# 2.net
KiCad netlist of a schematic drawn in EasyEDA Pro
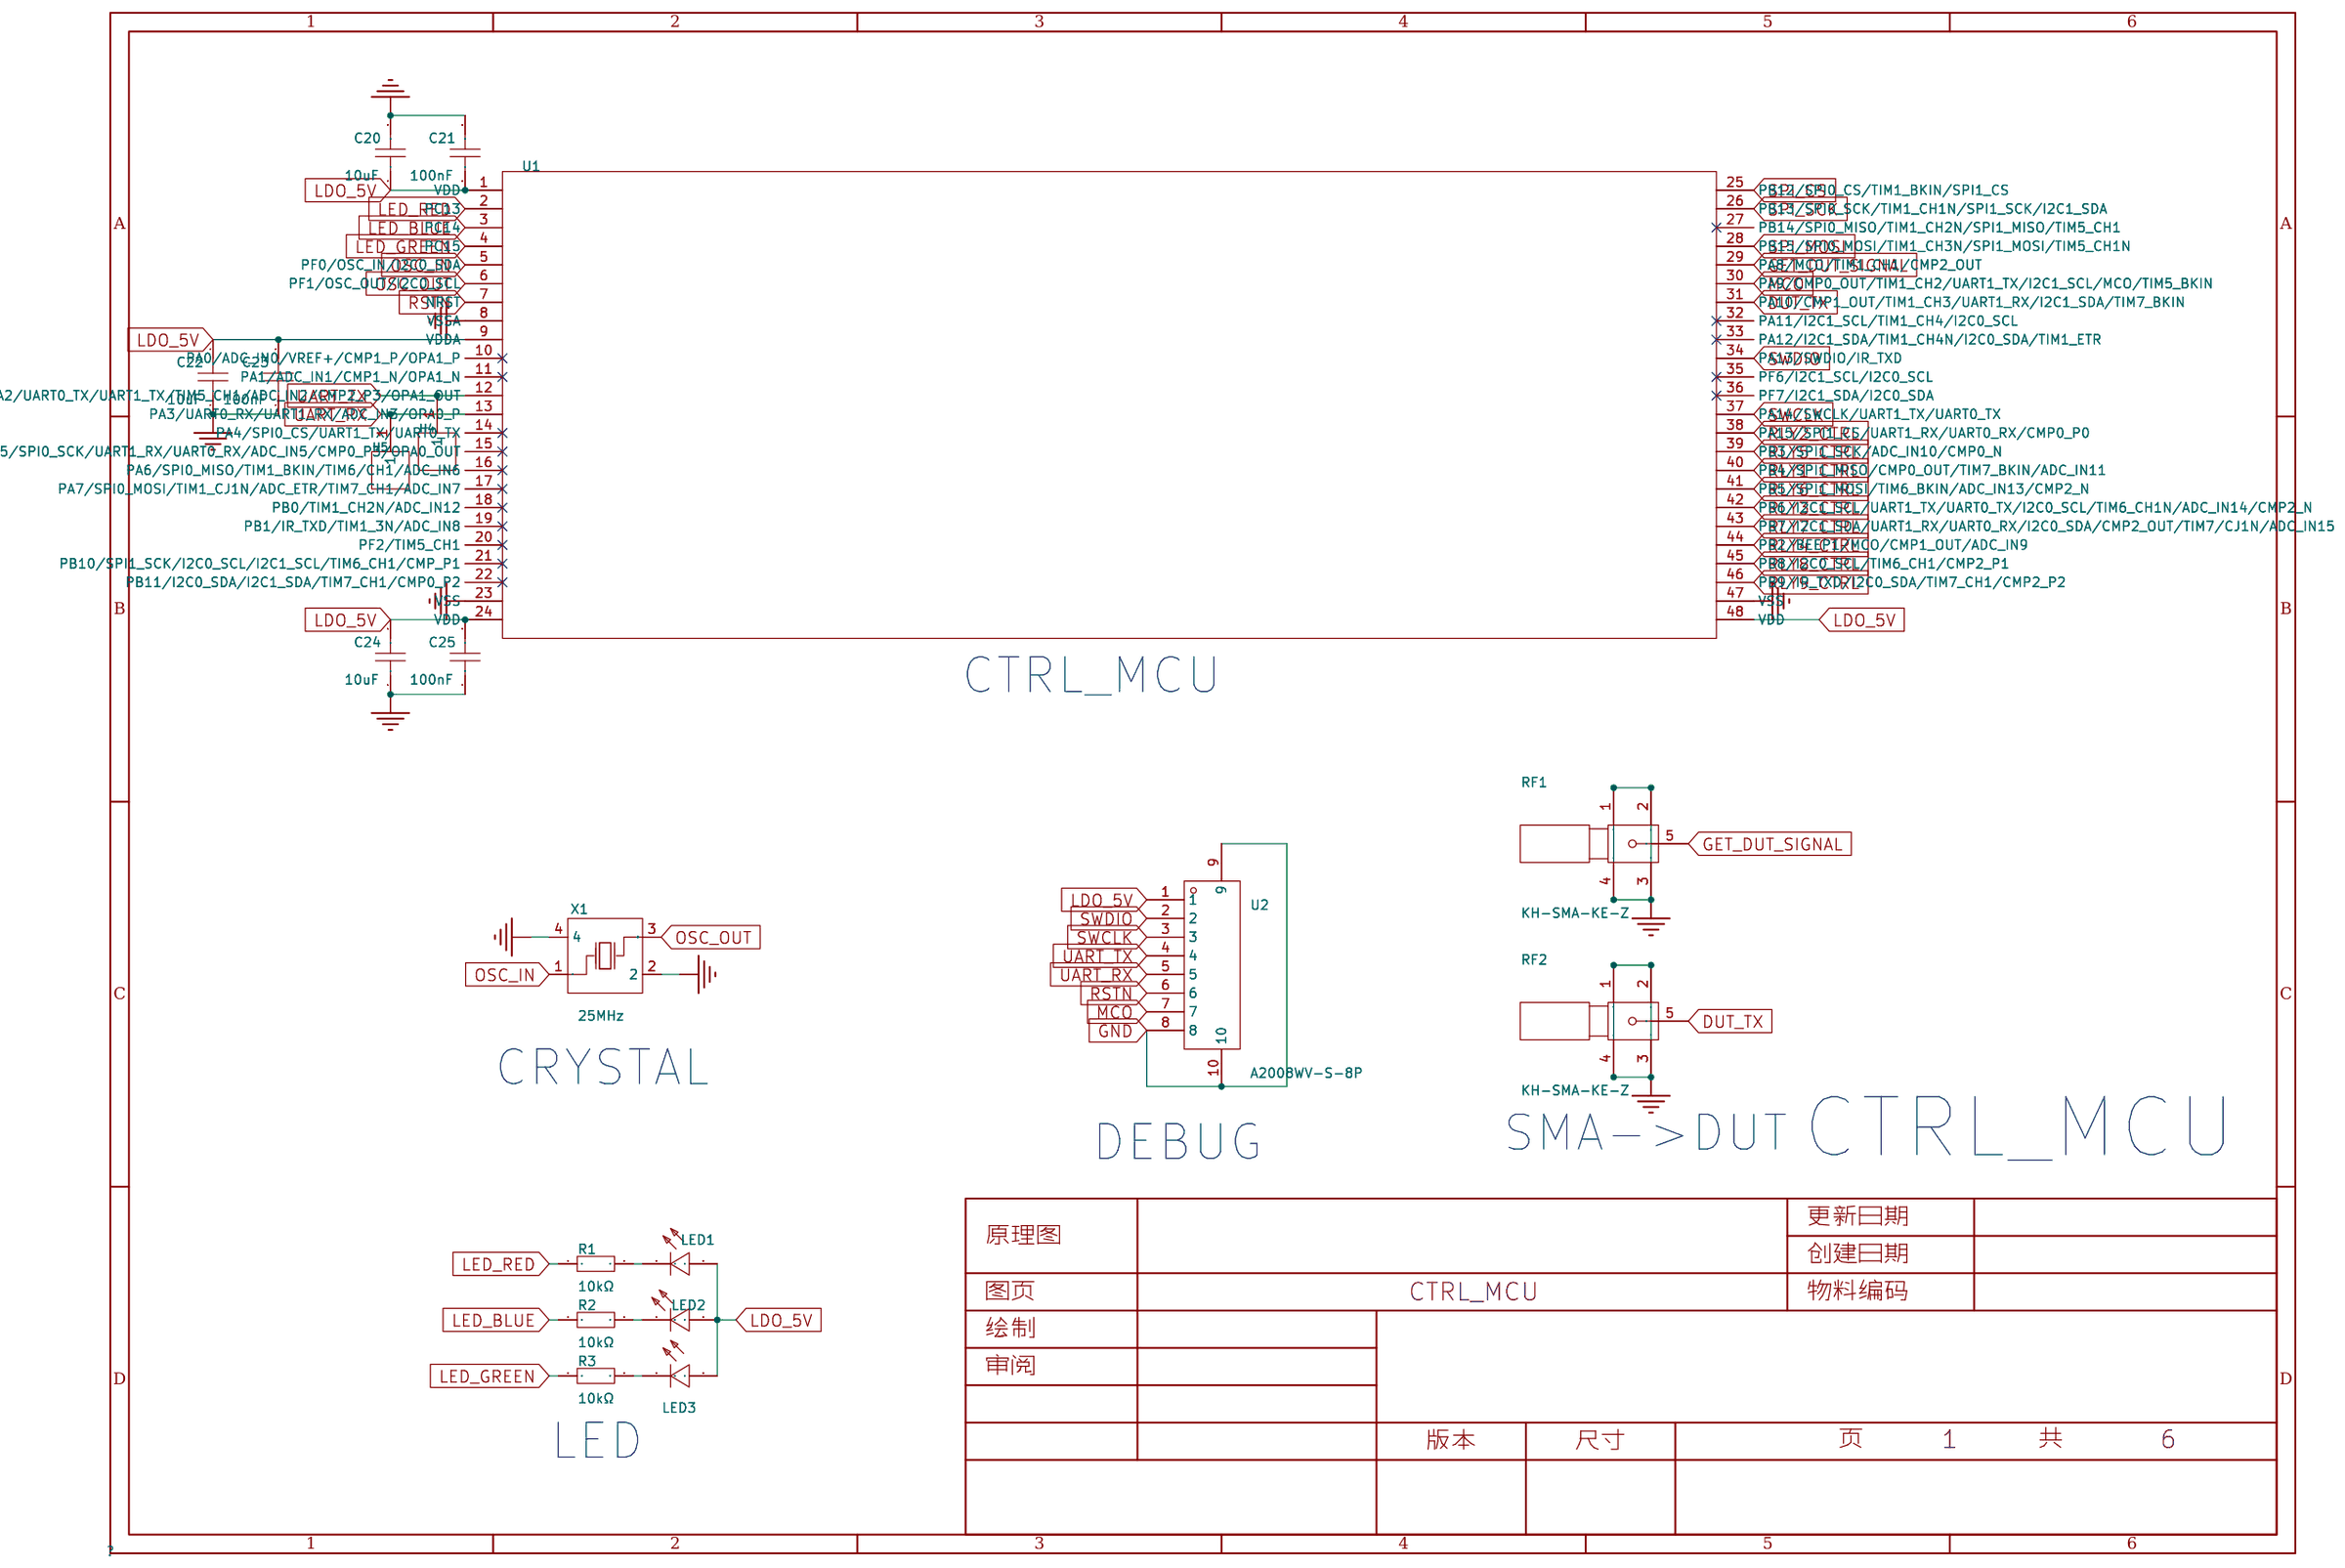
[diagram p0: CTRL_MCU]
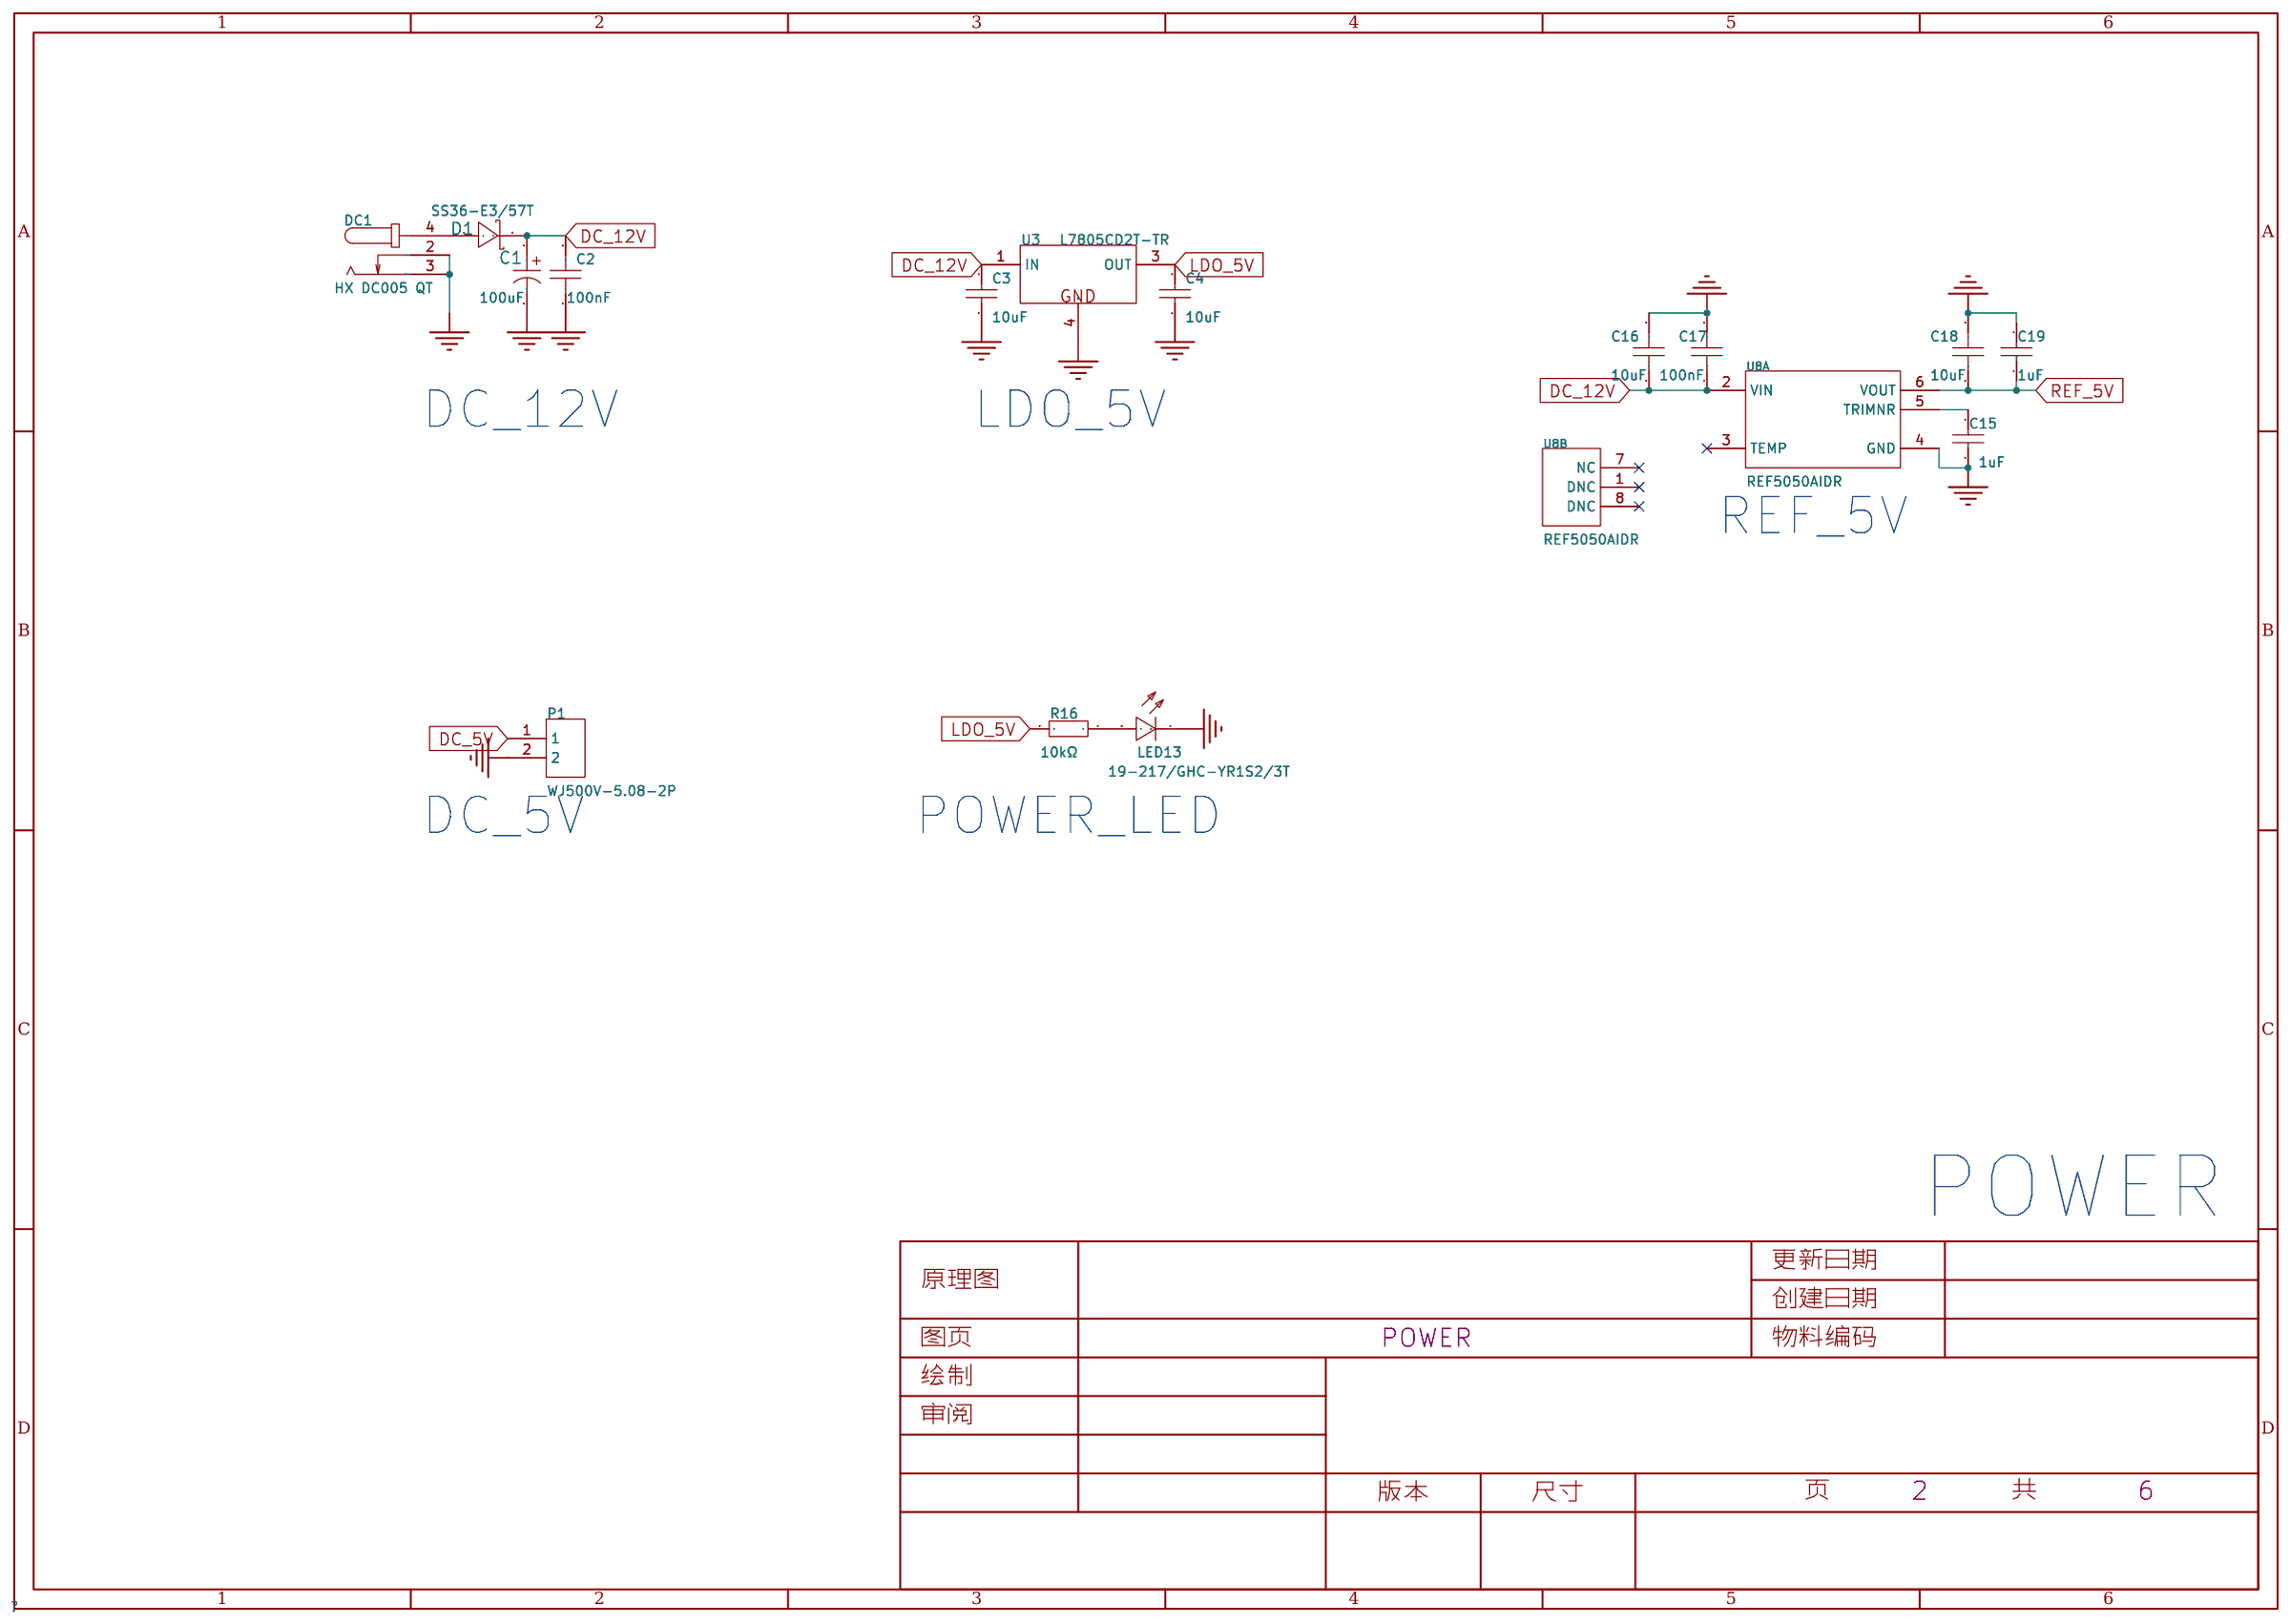
[diagram p1: POWER]
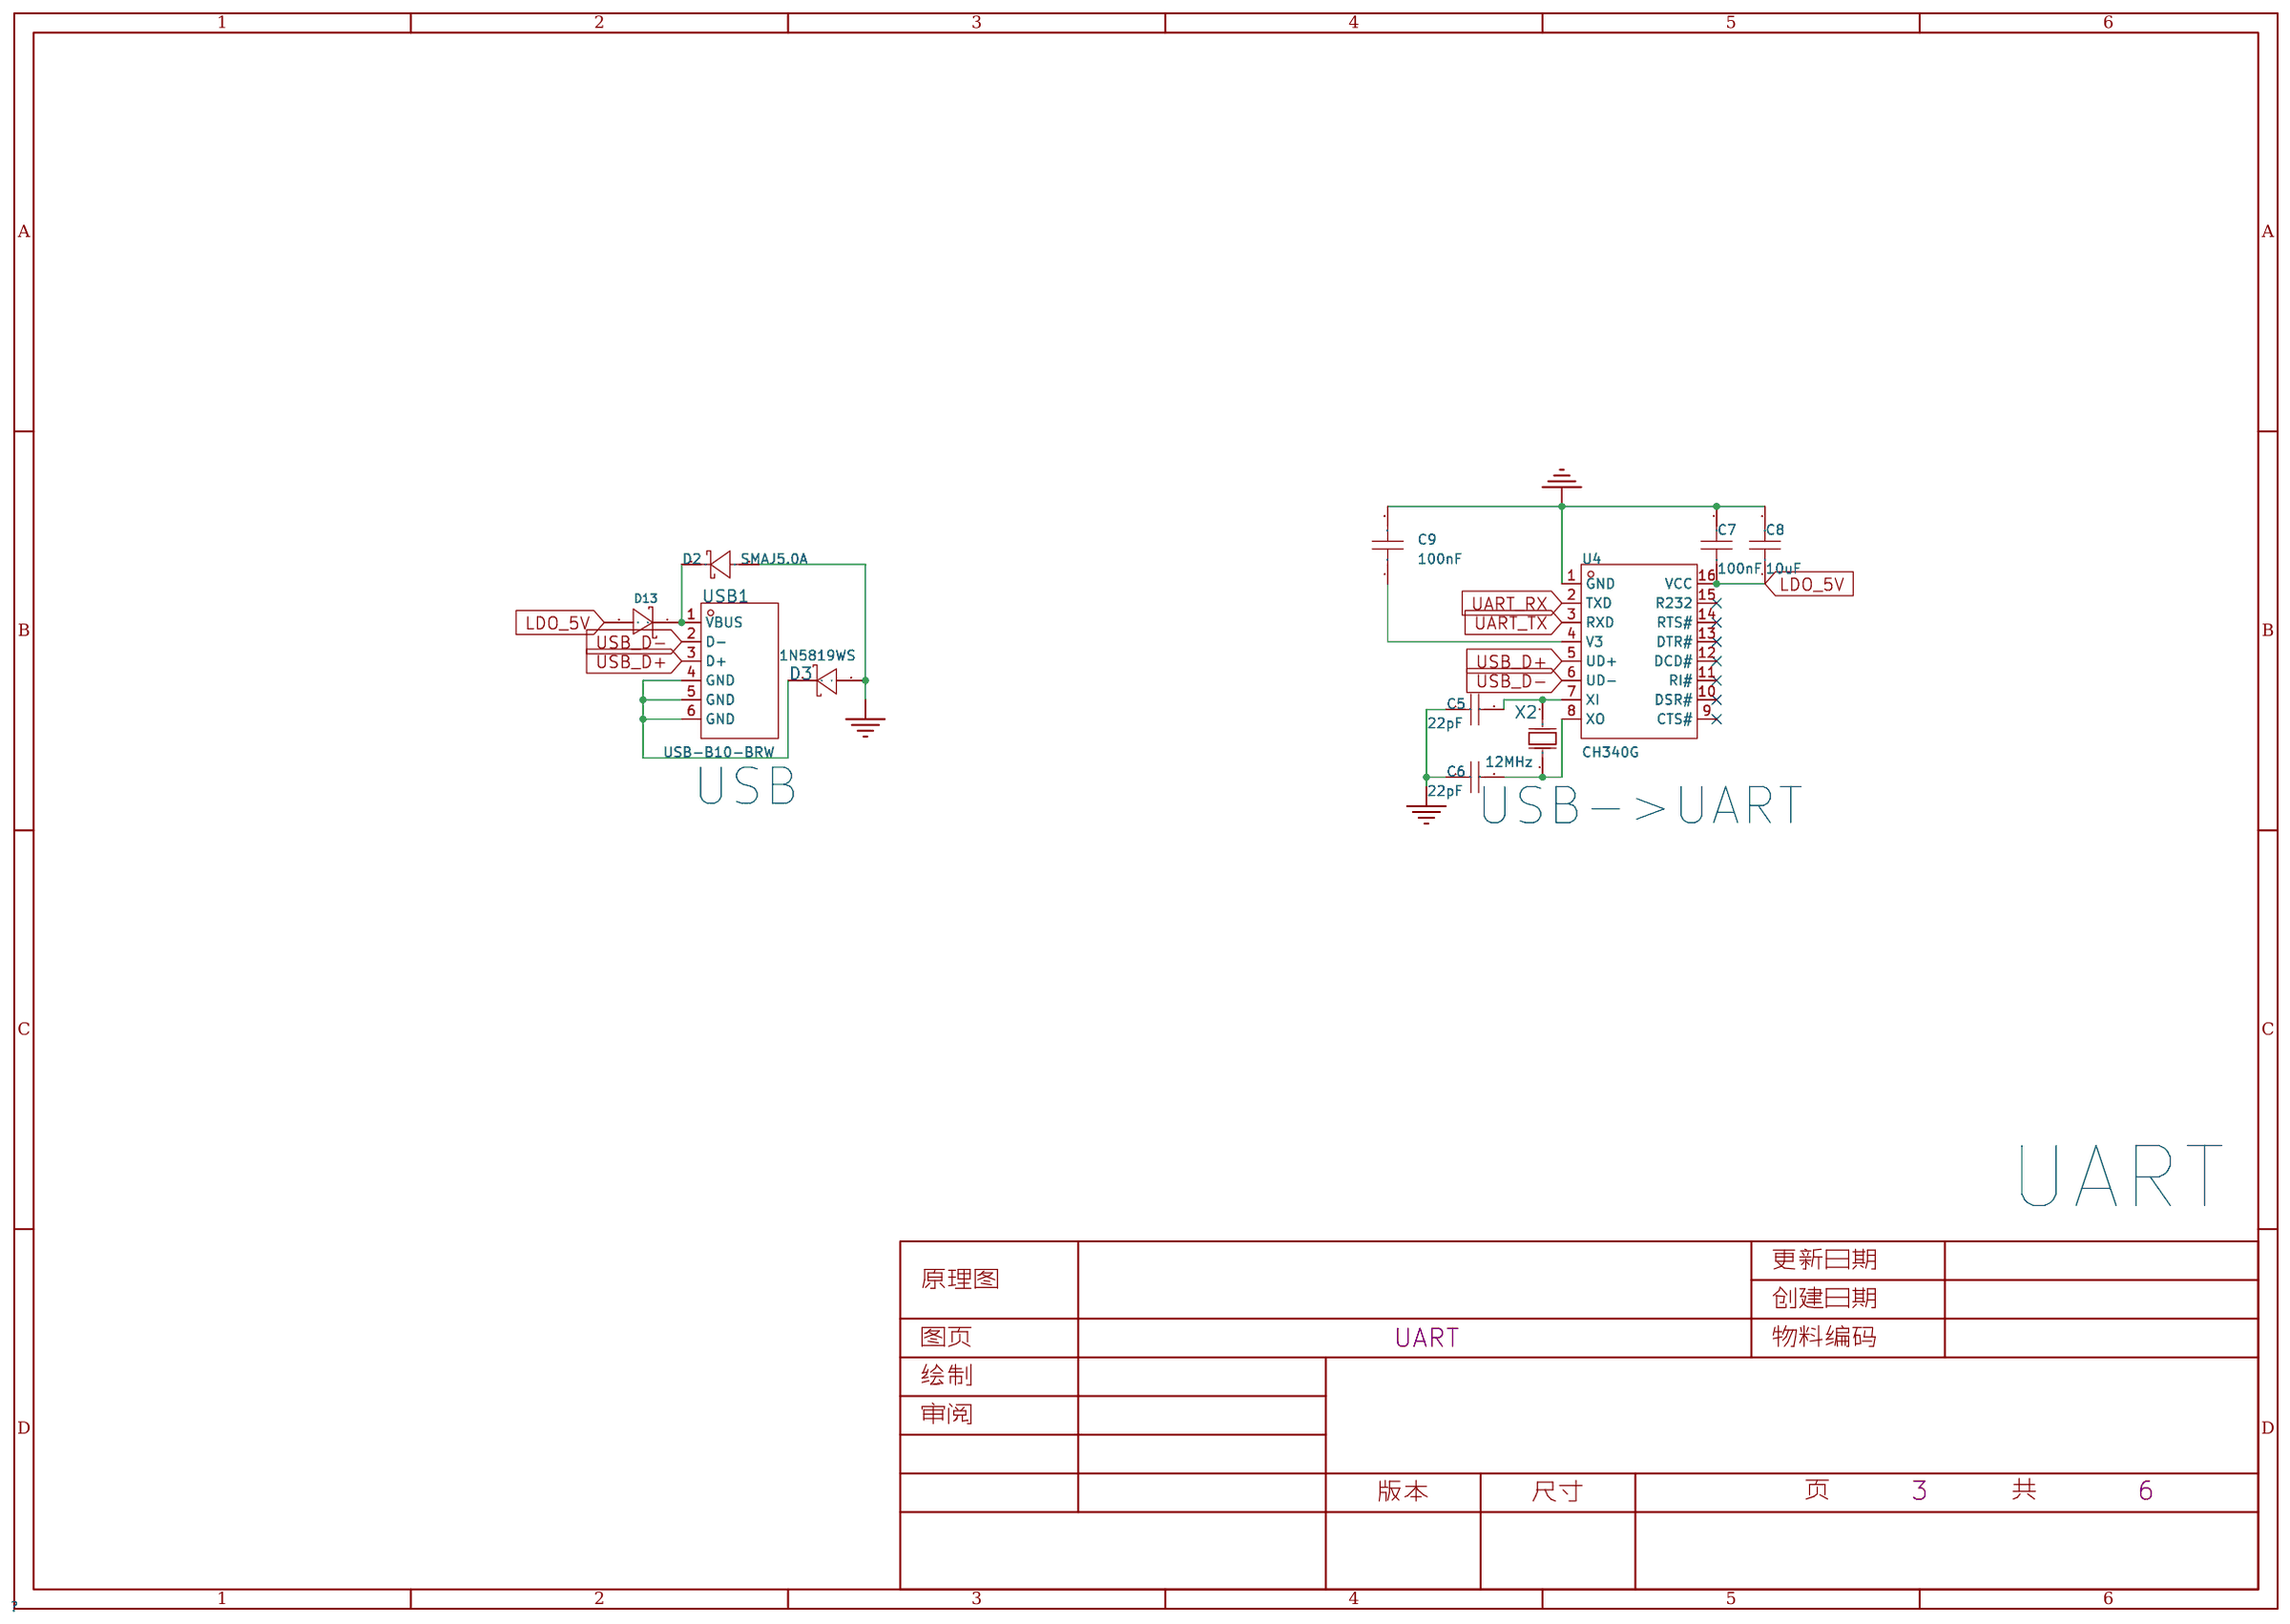
[diagram p2: UART]
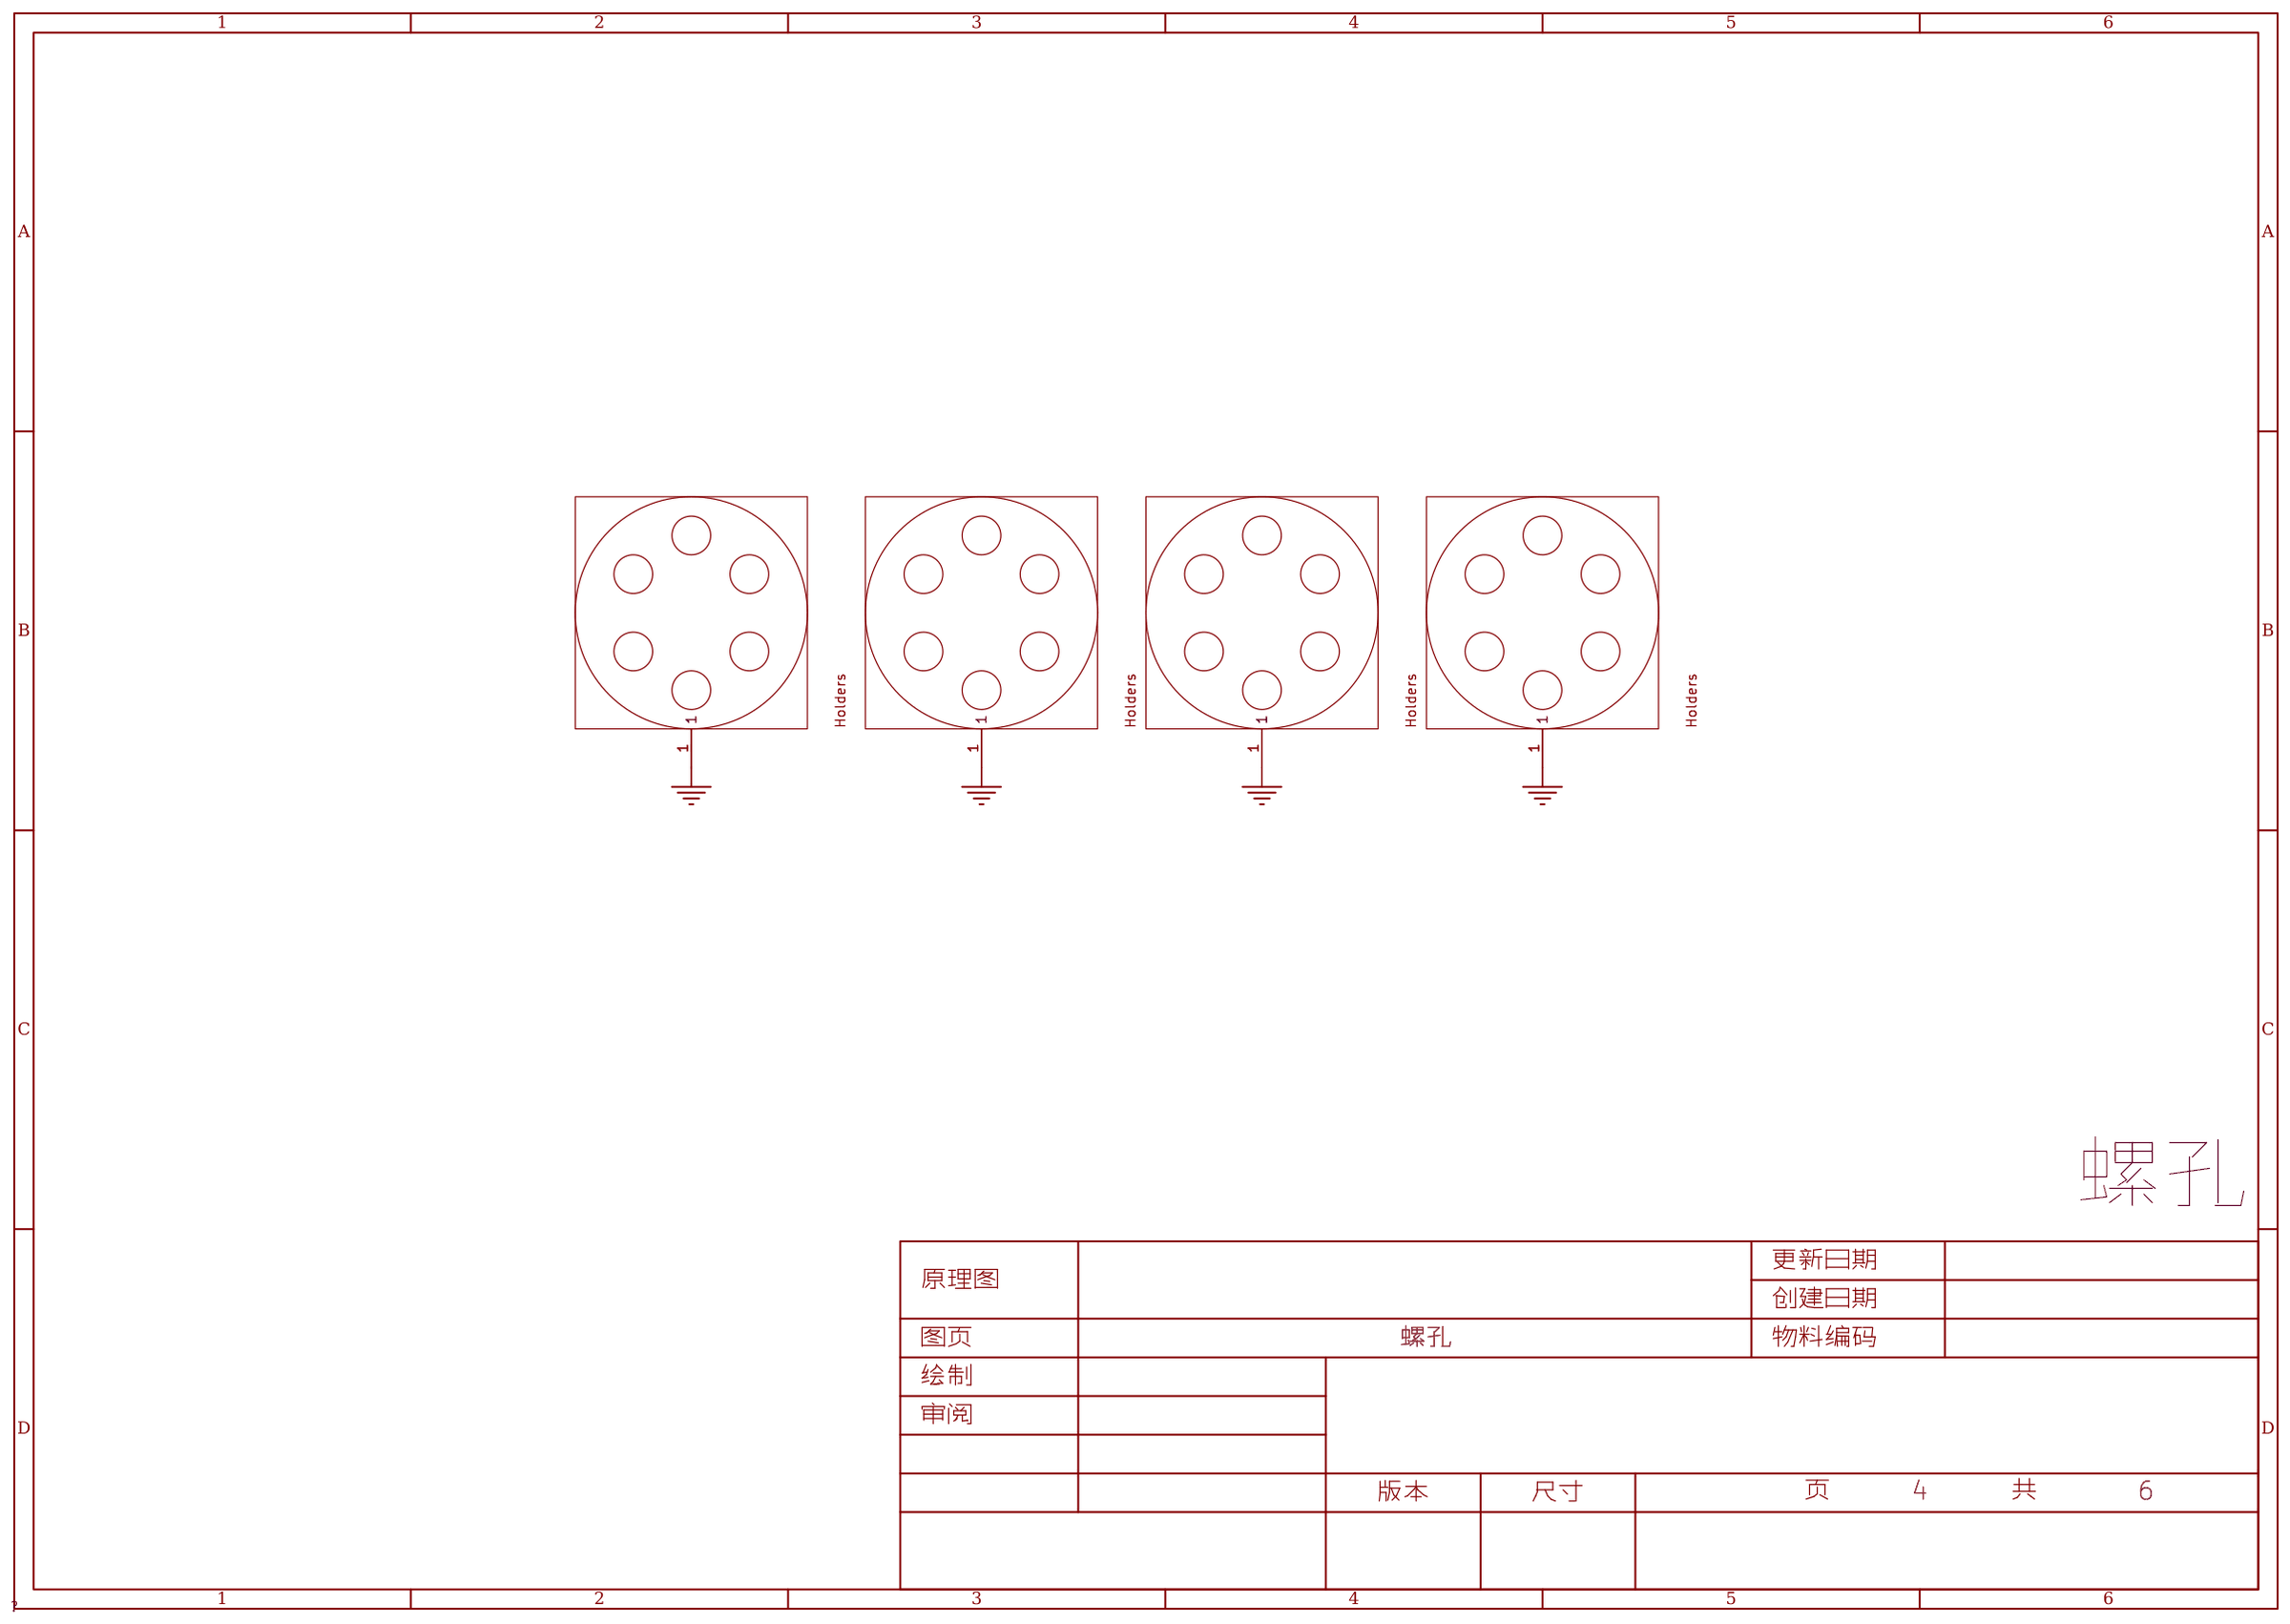
[diagram p3: 螺孔]
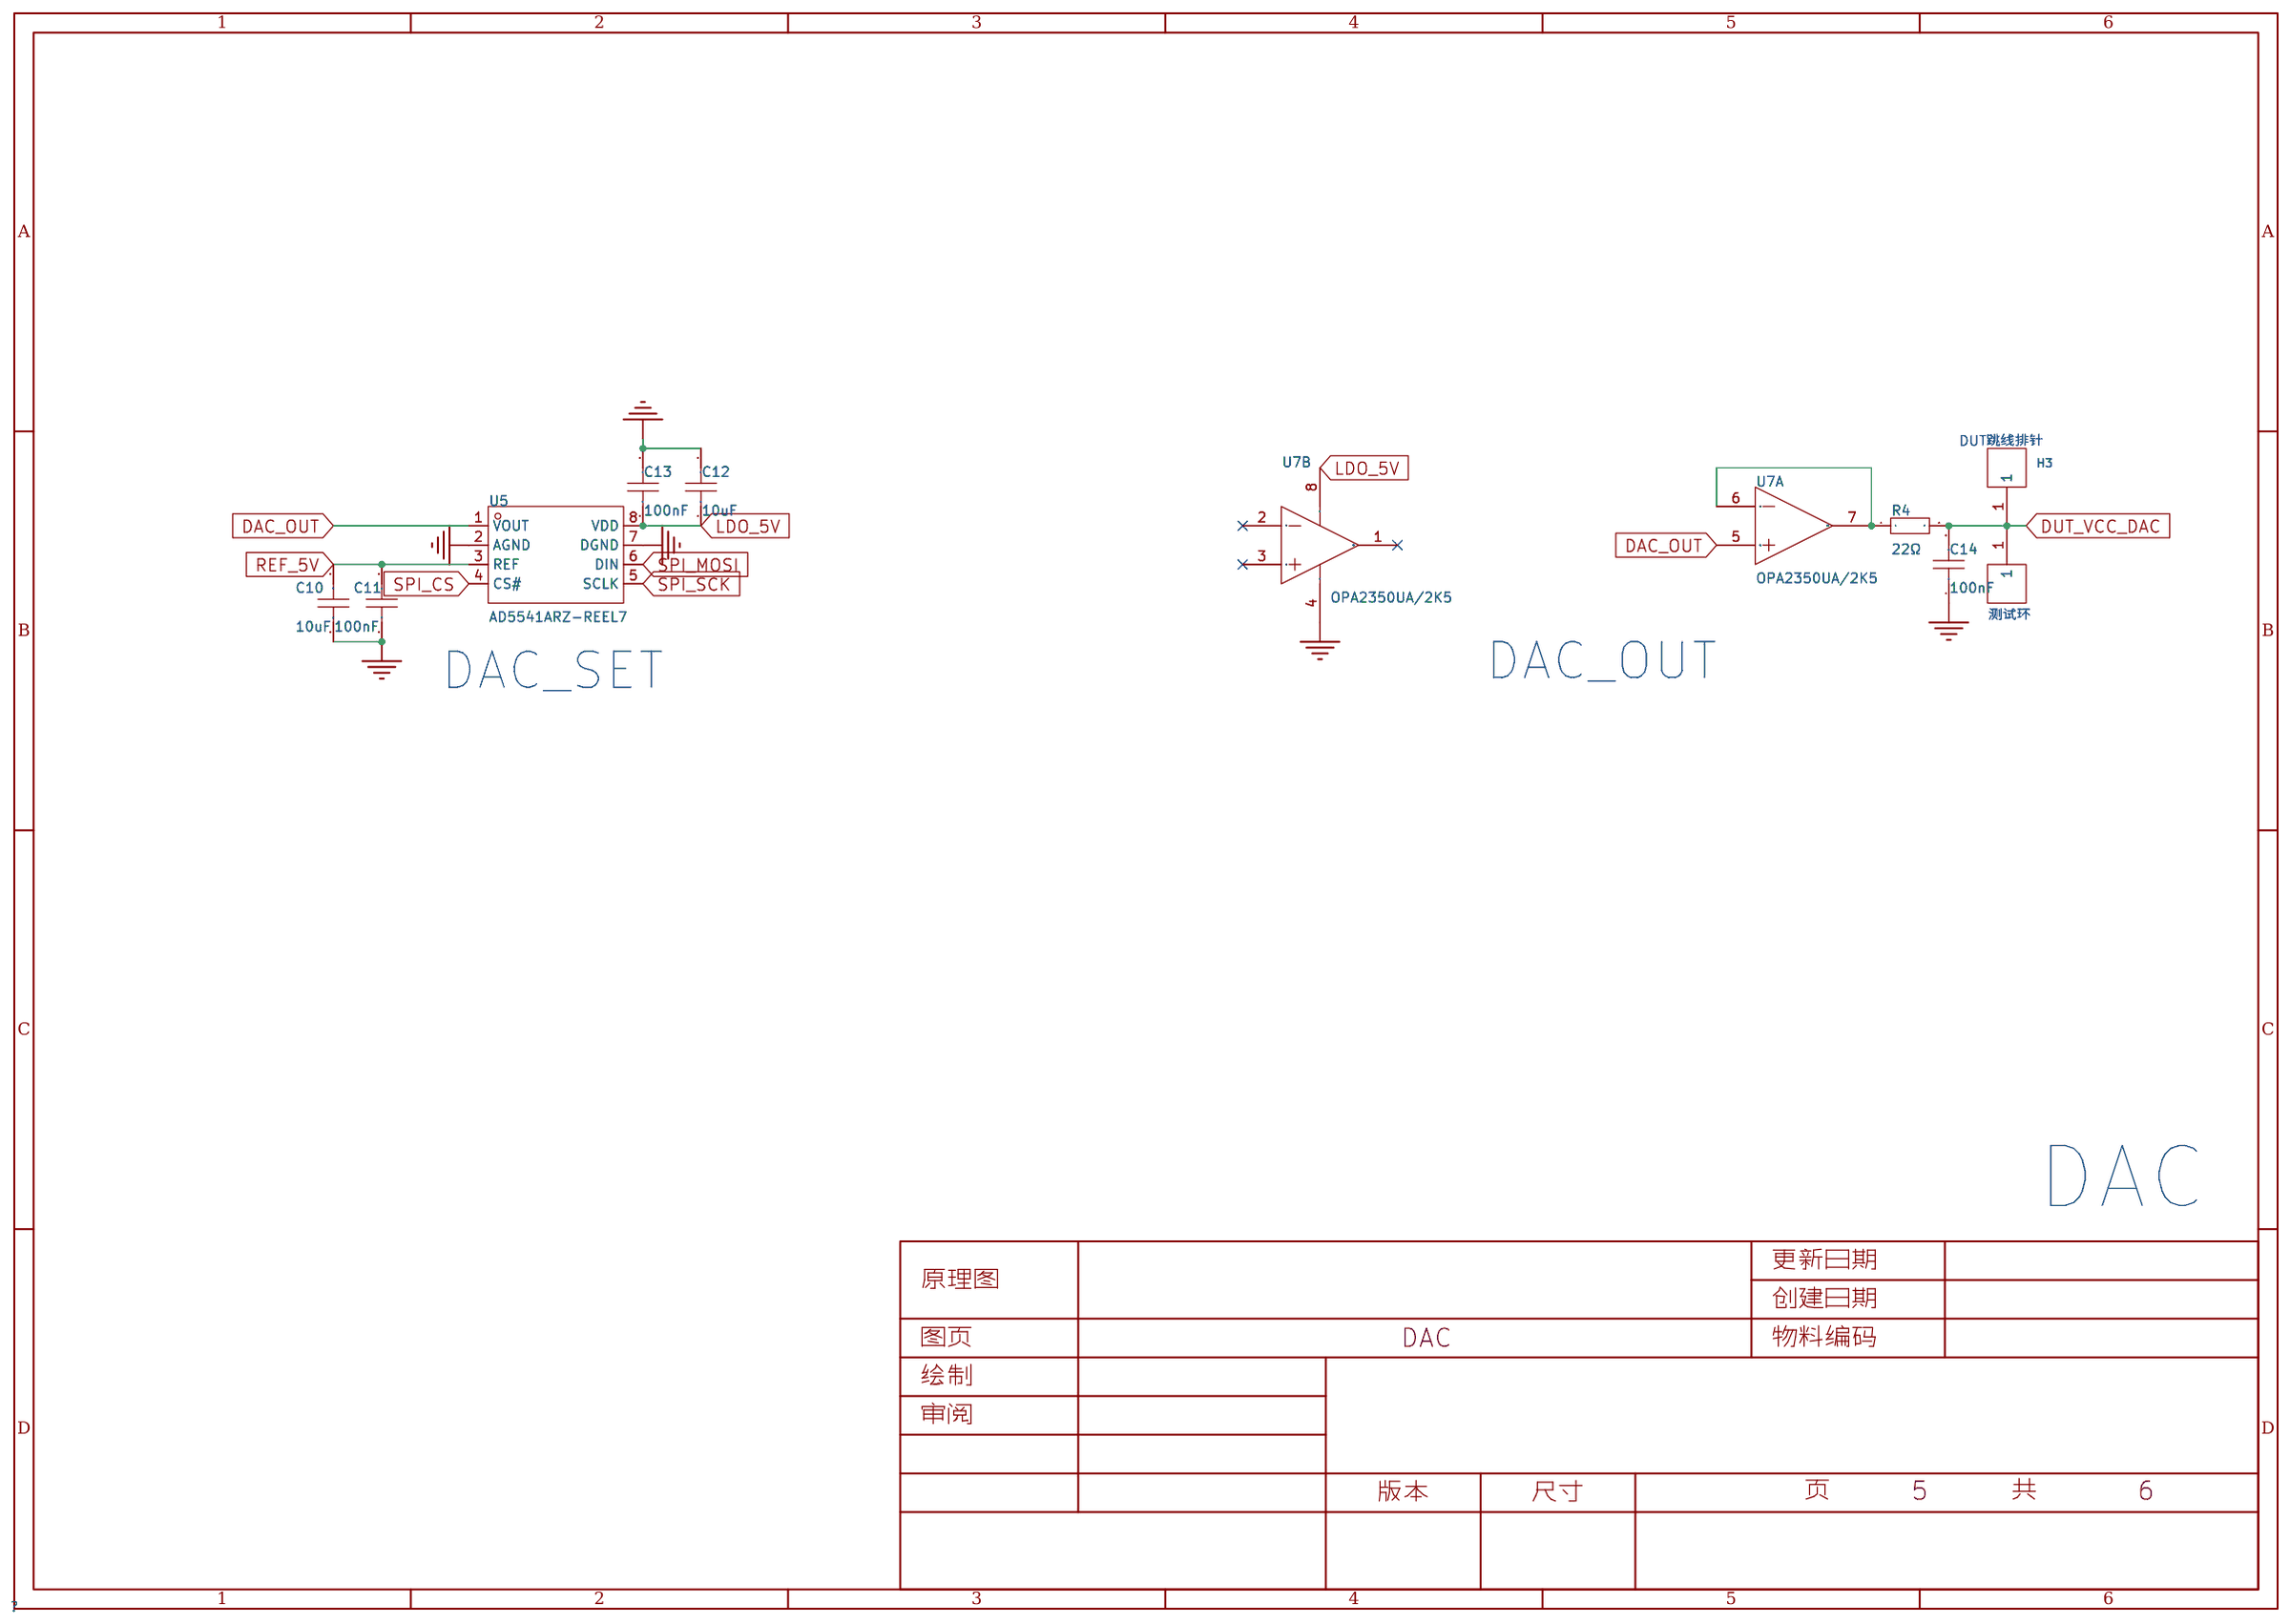
[diagram p4: DAC]
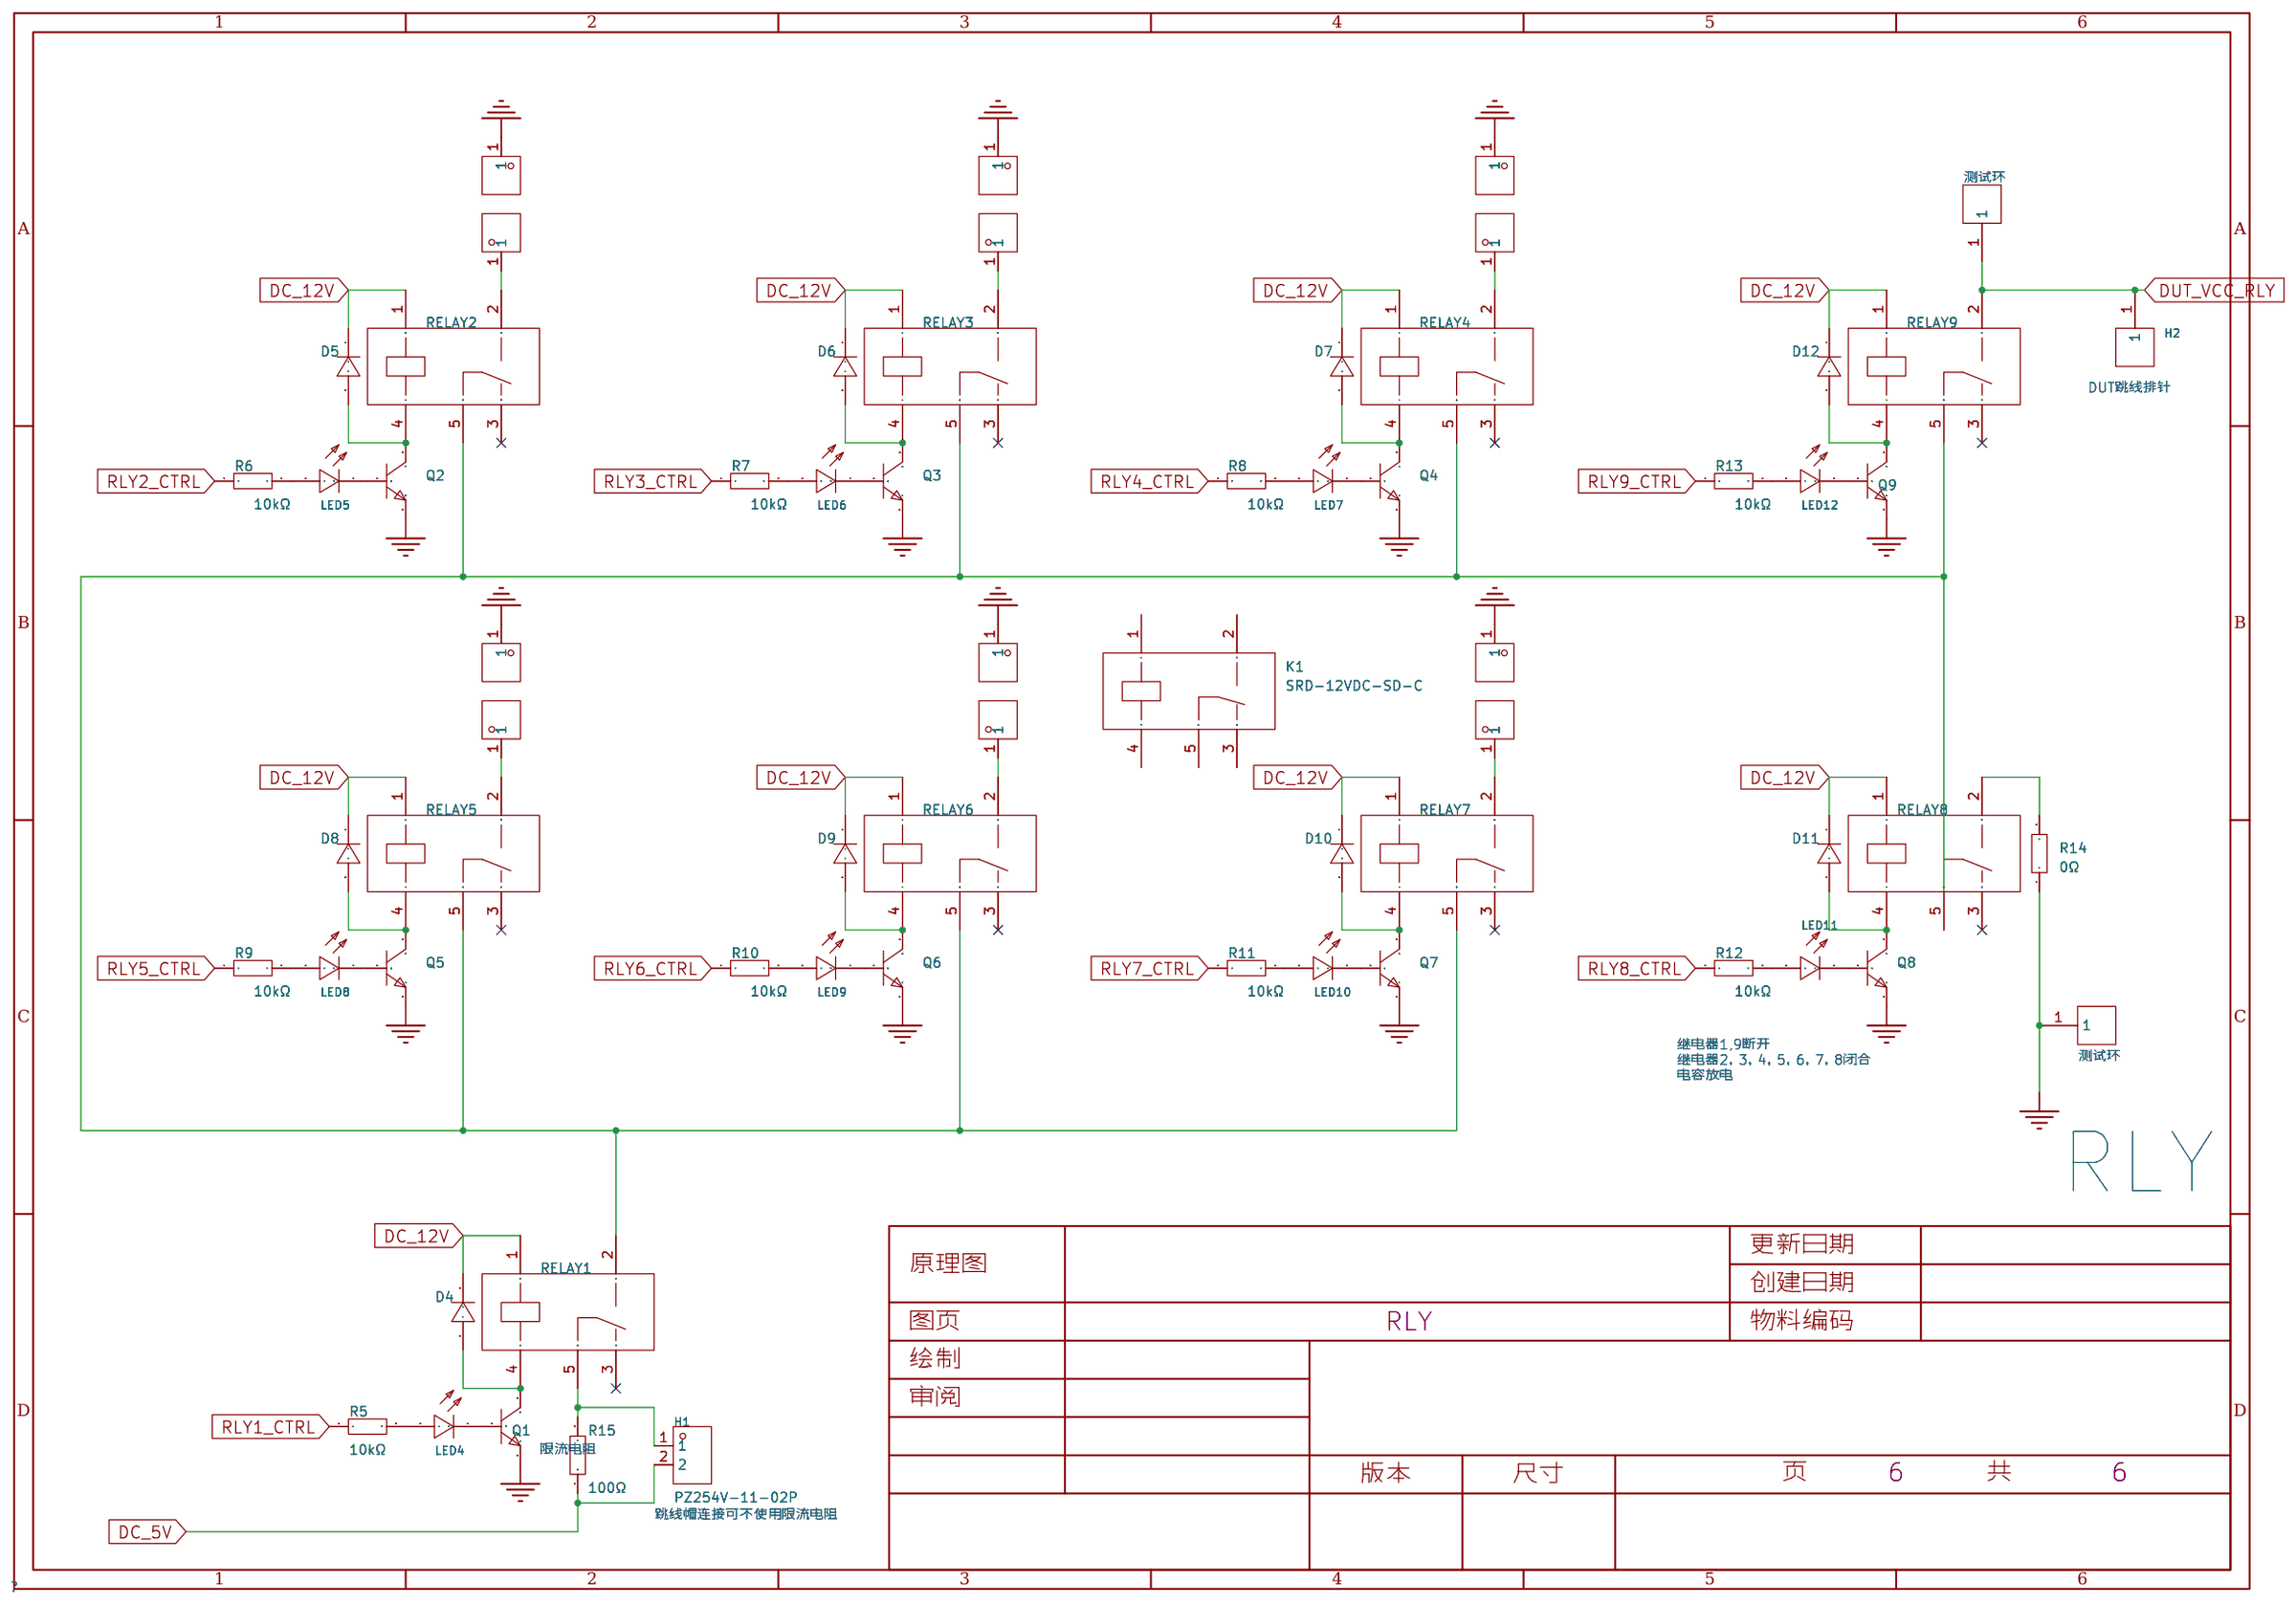
[diagram p5: RLY]

(export (version "E")
  (design (tool "Eeschema 10.0.6"))
  (components
    (comp (ref "C20")
      (value "10uF")
      (footprint "easyedapro:C0603")
      (description "容值:10uF;精度:±20%;额定电压:25V;材质(温度系数):X5R;")
      (fields
        (field (name "Manufacturer Part") "CL10A106MA8NRNC")
        (field (name "Manufacturer") "SAMSUNG(三星)")
      )
      (libsource (lib "easyedapro") (part "CL10A106MA8NRNC"))
    )
    (comp (ref "C21")
      (value "100nF")
      (footprint "easyedapro:C0603")
      (description "容值:100nF;精度:±10%;额定电压:50V;材质(温度系数):X7R;")
      (fields
        (field (name "Manufacturer Part") "CC0603KRX7R9BB104")
        (field (name "Manufacturer") "YAGEO(国巨)")
      )
      (libsource (lib "easyedapro") (part "CC0603KRX7R9BB104"))
    )
    (comp (ref "C22")
      (value "10uF")
      (footprint "easyedapro:C0603")
      (description "容值:10uF;精度:±20%;额定电压:25V;材质(温度系数):X5R;")
      (fields
        (field (name "Manufacturer Part") "CL10A106MA8NRNC")
        (field (name "Manufacturer") "SAMSUNG(三星)")
      )
      (libsource (lib "easyedapro") (part "CL10A106MA8NRNC"))
    )
    (comp (ref "C23")
      (value "100nF")
      (footprint "easyedapro:C0603")
      (description "容值:100nF;精度:±10%;额定电压:50V;材质(温度系数):X7R;")
      (fields
        (field (name "Manufacturer Part") "CC0603KRX7R9BB104")
        (field (name "Manufacturer") "YAGEO(国巨)")
      )
      (libsource (lib "easyedapro") (part "CC0603KRX7R9BB104"))
    )
    (comp (ref "C24")
      (value "10uF")
      (footprint "easyedapro:C0603")
      (description "容值:10uF;精度:±20%;额定电压:25V;材质(温度系数):X5R;")
      (fields
        (field (name "Manufacturer Part") "CL10A106MA8NRNC")
        (field (name "Manufacturer") "SAMSUNG(三星)")
      )
      (libsource (lib "easyedapro") (part "CL10A106MA8NRNC"))
    )
    (comp (ref "C25")
      (value "100nF")
      (footprint "easyedapro:C0603")
      (description "容值:100nF;精度:±10%;额定电压:50V;材质(温度系数):X7R;")
      (fields
        (field (name "Manufacturer Part") "CC0603KRX7R9BB104")
        (field (name "Manufacturer") "YAGEO(国巨)")
      )
      (libsource (lib "easyedapro") (part "CC0603KRX7R9BB104"))
    )
    (comp (ref "H4")
      (value "PZ254V-11-01P")
      (footprint "easyedapro:HDR-TH_1P-P2.54-V-M")
      (fields (field (name "Manufacturer") "XFCN(兴飞)"))
      (libsource (lib "easyedapro") (part "PZ254V-11-01P"))
    )
    (comp (ref "H5")
      (value "PZ254V-11-01P")
      (footprint "easyedapro:HDR-TH_1P-P2.54-V-M")
      (fields (field (name "Manufacturer") "XFCN(兴飞)"))
      (libsource (lib "easyedapro") (part "PZ254V-11-01P"))
    )
    (comp (ref "LED1")
      (value "NCD0603R1")
      (footprint "easyedapro:LED0603-RD_RED")
      (description "发光颜色:红灯;")
      (fields (field (name "Manufacturer") "国星光电"))
      (libsource (lib "easyedapro") (part "FC-DA1608HRK-620D"))
    )
    (comp (ref "LED2")
      (value "19-217/BHC-ZL1M2RY/3T")
      (footprint "easyedapro:LED0603-FD_BLUE")
      (description "发光颜色:蓝灯;二极管配置:-;主波长:465nm~475nm;色温:-;功率:110mW;安装方式:-;")
      (fields (field (name "Manufacturer") "EVERLIGHT(亿光)"))
      (libsource (lib "easyedapro") (part "19-217/BHC-ZL1M2RY/3T"))
    )
    (comp (ref "LED3")
      (value "19-217/GHC-YR1S2/3T")
      (footprint "easyedapro:LED0603-RD")
      (description "发光颜色:翠绿;二极管配置:-;主波长:520nm~535nm;色温:-;功率:110mW;安装方式:-;")
      (fields (field (name "Manufacturer") "EVERLIGHT(亿光)"))
      (libsource (lib "easyedapro") (part "19-217/GHC-YR1S2/3T"))
    )
    (comp (ref "R1")
      (value "10kΩ")
      (footprint "easyedapro:R0603")
      (description "电阻类型:厚膜电阻;阻值:10kΩ;精度:±1%;功率:100mW;")
      (fields
        (field (name "Manufacturer Part") "0603WAF1002T5E")
        (field (name "Manufacturer") "UNI-ROYAL(厚声)")
      )
      (libsource (lib "easyedapro") (part "0603WAF1002T5E"))
    )
    (comp (ref "R2")
      (value "10kΩ")
      (footprint "easyedapro:R0603")
      (description "电阻类型:厚膜电阻;阻值:10kΩ;精度:±1%;功率:100mW;")
      (fields
        (field (name "Manufacturer Part") "0603WAF1002T5E")
        (field (name "Manufacturer") "UNI-ROYAL(厚声)")
      )
      (libsource (lib "easyedapro") (part "0603WAF1002T5E"))
    )
    (comp (ref "R3")
      (value "10kΩ")
      (footprint "easyedapro:R0603")
      (description "电阻类型:厚膜电阻;阻值:10kΩ;精度:±1%;功率:100mW;")
      (fields
        (field (name "Manufacturer Part") "0603WAF1002T5E")
        (field (name "Manufacturer") "UNI-ROYAL(厚声)")
      )
      (libsource (lib "easyedapro") (part "0603WAF1002T5E"))
    )
    (comp (ref "RF1")
      (value "KH-SMA-KE-Z")
      (footprint "easyedapro:SMA-TH_KH-SMA-KE-Z")
      (description "连接器类型:板端;射频系列:SMA;接口类型:内孔;端口数量:1;阻抗:-;频率-最大值:-;样式:正脚;接口直径:6.2mm;接口长度/高度:8mm;工作温度范围:-;")
      (fields (field (name "Manufacturer") "kinghelm(金航标)"))
      (libsource (lib "easyedapro") (part "KH-SMA-KE-Z"))
    )
    (comp (ref "RF2")
      (value "KH-SMA-KE-Z")
      (footprint "easyedapro:SMA-TH_KH-SMA-KE-Z")
      (description "连接器类型:板端;射频系列:SMA;接口类型:内孔;端口数量:1;阻抗:-;频率-最大值:-;样式:正脚;接口直径:6.2mm;接口长度/高度:8mm;工作温度范围:-;")
      (fields (field (name "Manufacturer") "kinghelm(金航标)"))
      (libsource (lib "easyedapro") (part "KH-SMA-KE-Z"))
    )
    (comp (ref "U1") (value "PT32A030C8T7") (libsource (lib "easyedapro") (part "PT32A030C8T7")))
    (comp (ref "U2")
      (value "A2008WV-S-8P")
      (footprint "easyedapro:CONN-SMD_A2008WV-S-8P")
      (description "参考系列:PH;间距:2mm;插针结构:1x8P;排数:1;每排PIN数:8;行距:-;安装方式:-;触头材质:黄铜;")
      (fields (field (name "Manufacturer") "CJT(长江连接器)"))
      (libsource (lib "easyedapro") (part "A2008WV-S-8P"))
    )
    (comp (ref "X1")
      (value "25MHz")
      (footprint "easyedapro:OSC-SMD_4P-L2.5-W2.0-BL")
      (description "晶振类型:-;频率:25MHz;频率公差:±25ppm;频率稳定度:±50ppm;负载电容:10pF;等效串联电阻(ESR):60Ω;工作温度:-40°C~+125°C;")
      (fields (field (name "Manufacturer Part") "ECS-250-10-36Q-AES-TR") (field (name "Manufacturer") "ECS"))
      (libsource (lib "easyedapro") (part "ECS-250-10-36Q-AES-TR"))
    )
    (comp (ref "C1")
      (value "100uF")
      (footprint "easyedapro:CAP-SMD_BD6.3-L6.6-W6.6-LS7.6-FD-1")
      (description "容值:100uF;精度:±20%;额定电压:35V;纹波电流:230mA@120Hz;等效串联电阻:600mΩ@100kHz;")
      (fields
        (field (name "Manufacturer Part") "RVE100UF35V67RV0072")
        (field (name "Manufacturer") "KNSCHA(科尼盛)")
      )
      (libsource (lib "easyedapro") (part "RVE100UF35V67RV0072"))
    )
    (comp (ref "C2")
      (value "100nF")
      (footprint "easyedapro:C0603")
      (description "容值:100nF;精度:±10%;额定电压:50V;材质(温度系数):X7R;")
      (fields
        (field (name "Manufacturer Part") "CL10B104KB8NNNC")
        (field (name "Manufacturer") "SAMSUNG(三星)")
      )
      (libsource (lib "easyedapro") (part "CL10B104KB8NNNC"))
    )
    (comp (ref "C3")
      (value "10uF")
      (footprint "easyedapro:C1206")
      (description "容值:10uF;精度:±10%;额定电压:50V;材质(温度系数):X5R;")
      (fields
        (field (name "Manufacturer Part") "CL31A106KBHNNNE")
        (field (name "Manufacturer") "SAMSUNG(三星)")
      )
      (libsource (lib "easyedapro") (part "CL31A106KBHNNNE"))
    )
    (comp (ref "C4")
      (value "10uF")
      (footprint "easyedapro:C1206")
      (description "容值:10uF;精度:±10%;额定电压:50V;材质(温度系数):X5R;")
      (fields
        (field (name "Manufacturer Part") "CL31A106KBHNNNE")
        (field (name "Manufacturer") "SAMSUNG(三星)")
      )
      (libsource (lib "easyedapro") (part "CL31A106KBHNNNE"))
    )
    (comp (ref "C15")
      (value "1uF")
      (footprint "easyedapro:C0603")
      (description "容值:1uF;精度:±10%;额定电压:50V;材质(温度系数):X5R;")
      (fields
        (field (name "Manufacturer Part") "CL10A105KB8NNNC")
        (field (name "Manufacturer") "SAMSUNG(三星)")
      )
      (libsource (lib "easyedapro") (part "CL10A105KB8NNNC"))
    )
    (comp (ref "C16")
      (value "10uF")
      (footprint "easyedapro:C0603")
      (description "容值:10uF;精度:±20%;额定电压:25V;材质(温度系数):X5R;")
      (fields
        (field (name "Manufacturer Part") "CL10A106MA8NRNC")
        (field (name "Manufacturer") "SAMSUNG(三星)")
      )
      (libsource (lib "easyedapro") (part "CL10A106MA8NRNC"))
    )
    (comp (ref "C17")
      (value "100nF")
      (footprint "easyedapro:C0603")
      (description "容值:100nF;精度:±10%;额定电压:50V;材质(温度系数):X7R;")
      (fields
        (field (name "Manufacturer Part") "CC0603KRX7R9BB104")
        (field (name "Manufacturer") "YAGEO(国巨)")
      )
      (libsource (lib "easyedapro") (part "CC0603KRX7R9BB104"))
    )
    (comp (ref "C18")
      (value "10uF")
      (footprint "easyedapro:C0603")
      (description "容值:10uF;精度:±20%;额定电压:25V;材质(温度系数):X5R;")
      (fields
        (field (name "Manufacturer Part") "CL10A106MA8NRNC")
        (field (name "Manufacturer") "SAMSUNG(三星)")
      )
      (libsource (lib "easyedapro") (part "CL10A106MA8NRNC"))
    )
    (comp (ref "C19")
      (value "1uF")
      (footprint "easyedapro:C0603")
      (description "容值:1uF;精度:±10%;额定电压:50V;材质(温度系数):X5R;")
      (fields
        (field (name "Manufacturer Part") "CL10A105KB8NNNC")
        (field (name "Manufacturer") "SAMSUNG(三星)")
      )
      (libsource (lib "easyedapro") (part "CL10A105KB8NNNC"))
    )
    (comp (ref "D1")
      (value "SS36-E3/57T")
      (footprint "easyedapro:SMC_L7.1-W6.2-LS8.1-R-RD")
      (description "直流反向耐压（Vr）:60V;平均整流电流（Io）:3A;正向压降（Vf）:750mV @ 3A;")
      (fields (field (name "Manufacturer") "VISHAY(威世)"))
      (libsource (lib "easyedapro") (part "SS36-E3/57T"))
    )
    (comp (ref "DC1")
      (value "HX DC005 QT")
      (footprint "easyedapro:DC-IN-TH_HANXIA_HX-DC005-QT")
      (description "连接器类型:DC插座;安装方式:卧插;额定电流:1A;额定电压:12V;工作温度范围:-25°C~+85°C;")
      (fields (field (name "Manufacturer") "hanxia(韩下)"))
      (libsource (lib "easyedapro") (part "HX DC005 QT"))
    )
    (comp (ref "LED13")
      (value "19-217/GHC-YR1S2/3T")
      (footprint "easyedapro:LED0603-RD")
      (description "发光颜色:翠绿;二极管配置:-;主波长:520nm~535nm;色温:-;功率:110mW;安装方式:-;")
      (fields (field (name "Manufacturer") "EVERLIGHT(亿光)"))
      (libsource (lib "easyedapro") (part "19-217/GHC-YR1S2/3T"))
    )
    (comp (ref "P1")
      (value "WJ500V-5.08-2P")
      (footprint "easyedapro:CONN-TH_2P-P5.00_WJ500V-5.08-2P")
      (fields (field (name "Manufacturer") "KANGNEX(康奈克斯电气)"))
      (libsource (lib "easyedapro") (part "WJ500V-5.08-2P-14-00A"))
    )
    (comp (ref "R16")
      (value "10kΩ")
      (footprint "easyedapro:R0603")
      (description "电阻类型:厚膜电阻;阻值:10kΩ;精度:±1%;功率:100mW;")
      (fields
        (field (name "Manufacturer Part") "0603WAF1002T5E")
        (field (name "Manufacturer") "UNI-ROYAL(厚声)")
      )
      (libsource (lib "easyedapro") (part "0603WAF1002T5E"))
    )
    (comp (ref "U3")
      (value "L7805CD2T-TR")
      (footprint "easyedapro:TO-263-2_L10.0-W9.1-P5.08-LS15.2-TL")
      (description "输出类型:固定;输出极性:正;最大输入电压:35V;输出电压:5V;输出电流:1.5A;电源纹波抑制比(PSRR):62dB@(120Hz);")
      (fields (field (name "Manufacturer") "ST(意法半导体)"))
      (libsource (lib "easyedapro") (part "L7805CD2T-TR"))
    )
    (comp (ref "U8")
      (value "REF5050AIDR")
      (footprint "easyedapro:SOIC-8_L5.0-W4.0-P1.27-LS6.0-BL")
      (description "输出类型:固定;输入电压:5.2V~18V;输出电压:5V;输出电流:10mA;精度:±0.1%;")
      (fields (field (name "Manufacturer") "TI(德州仪器)"))
      (libsource (lib "easyedapro") (part "REF5050AIDR"))
    )
    (comp (ref "C5")
      (value "22pF")
      (footprint "easyedapro:C0603")
      (description "容值:22pF;精度:±5%;额定电压:50V;材质(温度系数):C0G;")
      (fields
        (field (name "Manufacturer Part") "CL10C220JB8NNNC")
        (field (name "Manufacturer") "SAMSUNG(三星)")
      )
      (libsource (lib "easyedapro") (part "CL10C220JB8NNNC"))
    )
    (comp (ref "C6")
      (value "22pF")
      (footprint "easyedapro:C0603")
      (description "容值:22pF;精度:±5%;额定电压:50V;材质(温度系数):C0G;")
      (fields
        (field (name "Manufacturer Part") "CL10C220JB8NNNC")
        (field (name "Manufacturer") "SAMSUNG(三星)")
      )
      (libsource (lib "easyedapro") (part "CL10C220JB8NNNC"))
    )
    (comp (ref "C7")
      (value "100nF")
      (footprint "easyedapro:C0603")
      (description "容值:100nF;精度:±10%;额定电压:50V;材质(温度系数):X7R;")
      (fields
        (field (name "Manufacturer Part") "CC0603KRX7R9BB104")
        (field (name "Manufacturer") "YAGEO(国巨)")
      )
      (libsource (lib "easyedapro") (part "CC0603KRX7R9BB104"))
    )
    (comp (ref "C8")
      (value "10uF")
      (footprint "easyedapro:C0603")
      (description "容值:10uF;精度:±10%;额定电压:10V;材质(温度系数):X5R;")
      (fields
        (field (name "Manufacturer Part") "CL10A106KP8NNNC")
        (field (name "Manufacturer") "SAMSUNG(三星)")
      )
      (libsource (lib "easyedapro") (part "CL10A106KP8NNNC"))
    )
    (comp (ref "C9")
      (value "100nF")
      (footprint "easyedapro:C0603")
      (description "容值:100nF;精度:±10%;额定电压:50V;材质(温度系数):X7R;")
      (fields
        (field (name "Manufacturer Part") "CC0603KRX7R9BB104")
        (field (name "Manufacturer") "YAGEO(国巨)")
      )
      (libsource (lib "easyedapro") (part "CC0603KRX7R9BB104"))
    )
    (comp (ref "D2")
      (value "SMAJ5.0A")
      (footprint "easyedapro:SMA_L4.3-W2.6-LS5.0-RD")
      (description "反向截止电压(Vrwm):5V;击穿电压:6.4V;最大钳位电压:9.2V;")
      (fields (field (name "Manufacturer") "Liown(里阳半导体)"))
      (libsource (lib "easyedapro") (part "SMAJ5.0A_C2925443"))
    )
    (comp (ref "D3")
      (value "1N5819WS")
      (footprint "easyedapro:SOD-323_L1.8-W1.3-LS2.5-RD")
      (description "直流反向耐压(Vr):40V;平均整流电流(Io):1A;正向压降(Vf):600mV@1A;")
      (fields (field (name "Manufacturer") "Hottech(合科泰)"))
      (libsource (lib "easyedapro") (part "1N5819WS"))
    )
    (comp (ref "D13")
      (value "1N5819WS")
      (footprint "easyedapro:SOD-323_L1.8-W1.3-LS2.5-RD")
      (description "直流反向耐压(Vr):40V;平均整流电流(Io):1A;正向压降(Vf):600mV@1A;")
      (fields (field (name "Manufacturer") "Hottech(合科泰)"))
      (libsource (lib "easyedapro") (part "1N5819WS"))
    )
    (comp (ref "U4")
      (value "CH340G")
      (footprint "easyedapro:SOIC-16_L9.9-W3.9-P1.27-LS6.0-BL")
      (description "应用功能:收发器;接口协议:USB 2.0;数据速率:2Mbps;")
      (fields (field (name "Manufacturer") "WCH(南京沁恒)"))
      (libsource (lib "easyedapro") (part "CH340G"))
    )
    (comp (ref "USB1")
      (value "USB-B10-BRW")
      (footprint "easyedapro:USB-B-TH_USB-B10-BRW")
      (fields (field (name "Manufacturer") "XUNPU(讯普)"))
      (libsource (lib "easyedapro") (part "USB-B10-BRW"))
    )
    (comp (ref "X2")
      (value "12MHz")
      (footprint "easyedapro:HC-49US_L11.5-W4.5-P4.88")
      (description "频率:12MHz;频率公差:±20ppm;负载电容:20pF;")
      (fields (field (name "Manufacturer Part") "X49SD12MSD2SC") (field (name "Manufacturer") "YXC(扬兴晶振)"))
      (libsource (lib "easyedapro") (part "X49SD12MSD2SC"))
    )
    (comp (ref "J2")
      (value "~")
      (footprint "easyedapro:DEMO板安装孔")
      (libsource (lib "easyedapro") (part "螺孔_3.1X6MM"))
    )
    (comp (ref "J3")
      (value "~")
      (footprint "easyedapro:DEMO板安装孔")
      (libsource (lib "easyedapro") (part "螺孔_3.1X6MM"))
    )
    (comp (ref "J4")
      (value "~")
      (footprint "easyedapro:DEMO板安装孔")
      (libsource (lib "easyedapro") (part "螺孔_3.1X6MM"))
    )
    (comp (ref "J5")
      (value "~")
      (footprint "easyedapro:DEMO板安装孔")
      (libsource (lib "easyedapro") (part "螺孔_3.1X6MM"))
    )
    (comp (ref "C10")
      (value "10uF")
      (footprint "easyedapro:C0603")
      (description "容值:10uF;精度:±20%;额定电压:25V;材质(温度系数):X5R;")
      (fields
        (field (name "Manufacturer Part") "CL10A106MA8NRNC")
        (field (name "Manufacturer") "SAMSUNG(三星)")
      )
      (libsource (lib "easyedapro") (part "CL10A106MA8NRNC"))
    )
    (comp (ref "C11")
      (value "100nF")
      (footprint "easyedapro:C0603")
      (description "容值:100nF;精度:±10%;额定电压:50V;材质(温度系数):X7R;")
      (fields
        (field (name "Manufacturer Part") "CC0603KRX7R9BB104")
        (field (name "Manufacturer") "YAGEO(国巨)")
      )
      (libsource (lib "easyedapro") (part "CC0603KRX7R9BB104"))
    )
    (comp (ref "C12")
      (value "10uF")
      (footprint "easyedapro:C0603")
      (description "容值:10uF;精度:±20%;额定电压:25V;材质(温度系数):X5R;")
      (fields
        (field (name "Manufacturer Part") "CL10A106MA8NRNC")
        (field (name "Manufacturer") "SAMSUNG(三星)")
      )
      (libsource (lib "easyedapro") (part "CL10A106MA8NRNC"))
    )
    (comp (ref "C13")
      (value "100nF")
      (footprint "easyedapro:C0603")
      (description "容值:100nF;精度:±10%;额定电压:50V;材质(温度系数):X7R;")
      (fields
        (field (name "Manufacturer Part") "CC0603KRX7R9BB104")
        (field (name "Manufacturer") "YAGEO(国巨)")
      )
      (libsource (lib "easyedapro") (part "CC0603KRX7R9BB104"))
    )
    (comp (ref "C14")
      (value "100nF")
      (footprint "easyedapro:C0603")
      (description "容值:100nF;精度:±10%;额定电压:50V;材质(温度系数):X7R;")
      (fields
        (field (name "Manufacturer Part") "CC0603KRX7R9BB104")
        (field (name "Manufacturer") "YAGEO(国巨)")
      )
      (libsource (lib "easyedapro") (part "CC0603KRX7R9BB104"))
    )
    (comp (ref "H3")
      (value "PZ254V-11-01P")
      (footprint "easyedapro:HDR-TH_1P-P2.54-V-M")
      (fields (field (name "Manufacturer") "XFCN(兴飞)"))
      (libsource (lib "easyedapro") (part "PZ254V-11-01P"))
    )
    (comp (ref "R4")
      (value "22Ω")
      (footprint "easyedapro:R0603")
      (description "电阻类型:厚膜电阻;阻值:22Ω;精度:±1%;功率:100mW;")
      (fields
        (field (name "Manufacturer Part") "0603WAF220JT5E")
        (field (name "Manufacturer") "UNI-ROYAL(厚声)")
      )
      (libsource (lib "easyedapro") (part "0603WAF220JT5E"))
    )
    (comp (ref "U5")
      (value "AD5541ARZ-REEL7")
      (footprint "easyedapro:SOIC-8_L5.0-W4.0-P1.27-LS6.0-BL")
      (description "D/A 位数:-;D/A通道数:-;输出类型:-;读写接口类型:-;")
      (fields (field (name "Manufacturer") "ADI(亚德诺)/LINEAR"))
      (libsource (lib "easyedapro") (part "AD5541ARZ-REEL7"))
    )
    (comp (ref "U7")
      (value "OPA2350UA/2K5")
      (footprint "easyedapro:SOIC-8_L4.9-W3.9-P1.27-LS6.0-BL")
      (description "放大器组数:2;输入偏置电流(Ib):0.5pA;增益带宽积(GBP):38MHz;压摆率(SR):22V/us;轨到轨:轨到轨;")
      (fields (field (name "Manufacturer") "TI(德州仪器)"))
      (libsource (lib "easyedapro") (part "OPA2350UA/2K5"))
    )
    (comp (ref "U40")
      (value "RH-5000")
      (footprint "easyedapro:TEST-TH_BD2.54-P1.4_RED")
      (description "100x80mm")
      (fields (field (name "Manufacturer") "荣和"))
      (libsource (lib "easyedapro") (part "RH-5000"))
    )
    (comp (ref "D4")
      (value "1N4148WS")
      (footprint "easyedapro:SOD-323_L1.8-W1.3-LS2.5-RD")
      (description "二极管配置:独立式;功率:200mW;直流反向耐压(Vr):100V;平均整流电流(Io):150mA;正向压降(Vf):1.25V@150mA;反向恢复时间(trr):4ns;")
      (fields (field (name "Manufacturer") "CJ(江苏长电/长晶)"))
      (libsource (lib "easyedapro") (part "1N4148WS T4"))
    )
    (comp (ref "D5")
      (value "1N4148WS")
      (footprint "easyedapro:SOD-323_L1.8-W1.3-LS2.5-RD")
      (description "二极管配置:独立式;功率:200mW;直流反向耐压(Vr):100V;平均整流电流(Io):150mA;正向压降(Vf):1.25V@150mA;反向恢复时间(trr):4ns;")
      (fields (field (name "Manufacturer") "CJ(江苏长电/长晶)"))
      (libsource (lib "easyedapro") (part "1N4148WS T4"))
    )
    (comp (ref "D6")
      (value "1N4148WS")
      (footprint "easyedapro:SOD-323_L1.8-W1.3-LS2.5-RD")
      (description "二极管配置:独立式;功率:200mW;直流反向耐压(Vr):100V;平均整流电流(Io):150mA;正向压降(Vf):1.25V@150mA;反向恢复时间(trr):4ns;")
      (fields (field (name "Manufacturer") "CJ(江苏长电/长晶)"))
      (libsource (lib "easyedapro") (part "1N4148WS T4"))
    )
    (comp (ref "D7")
      (value "1N4148WS")
      (footprint "easyedapro:SOD-323_L1.8-W1.3-LS2.5-RD")
      (description "二极管配置:独立式;功率:200mW;直流反向耐压(Vr):100V;平均整流电流(Io):150mA;正向压降(Vf):1.25V@150mA;反向恢复时间(trr):4ns;")
      (fields (field (name "Manufacturer") "CJ(江苏长电/长晶)"))
      (libsource (lib "easyedapro") (part "1N4148WS T4"))
    )
    (comp (ref "D8")
      (value "1N4148WS")
      (footprint "easyedapro:SOD-323_L1.8-W1.3-LS2.5-RD")
      (description "二极管配置:独立式;功率:200mW;直流反向耐压(Vr):100V;平均整流电流(Io):150mA;正向压降(Vf):1.25V@150mA;反向恢复时间(trr):4ns;")
      (fields (field (name "Manufacturer") "CJ(江苏长电/长晶)"))
      (libsource (lib "easyedapro") (part "1N4148WS T4"))
    )
    (comp (ref "D9")
      (value "1N4148WS")
      (footprint "easyedapro:SOD-323_L1.8-W1.3-LS2.5-RD")
      (description "二极管配置:独立式;功率:200mW;直流反向耐压(Vr):100V;平均整流电流(Io):150mA;正向压降(Vf):1.25V@150mA;反向恢复时间(trr):4ns;")
      (fields (field (name "Manufacturer") "CJ(江苏长电/长晶)"))
      (libsource (lib "easyedapro") (part "1N4148WS T4"))
    )
    (comp (ref "D10")
      (value "1N4148WS")
      (footprint "easyedapro:SOD-323_L1.8-W1.3-LS2.5-RD")
      (description "二极管配置:独立式;功率:200mW;直流反向耐压(Vr):100V;平均整流电流(Io):150mA;正向压降(Vf):1.25V@150mA;反向恢复时间(trr):4ns;")
      (fields (field (name "Manufacturer") "CJ(江苏长电/长晶)"))
      (libsource (lib "easyedapro") (part "1N4148WS T4"))
    )
    (comp (ref "D11")
      (value "1N4148WS")
      (footprint "easyedapro:SOD-323_L1.8-W1.3-LS2.5-RD")
      (description "二极管配置:独立式;功率:200mW;直流反向耐压(Vr):100V;平均整流电流(Io):150mA;正向压降(Vf):1.25V@150mA;反向恢复时间(trr):4ns;")
      (fields (field (name "Manufacturer") "CJ(江苏长电/长晶)"))
      (libsource (lib "easyedapro") (part "1N4148WS T4"))
    )
    (comp (ref "D12")
      (value "1N4148WS")
      (footprint "easyedapro:SOD-323_L1.8-W1.3-LS2.5-RD")
      (description "二极管配置:独立式;功率:200mW;直流反向耐压(Vr):100V;平均整流电流(Io):150mA;正向压降(Vf):1.25V@150mA;反向恢复时间(trr):4ns;")
      (fields (field (name "Manufacturer") "CJ(江苏长电/长晶)"))
      (libsource (lib "easyedapro") (part "1N4148WS T4"))
    )
    (comp (ref "H1")
      (value "PZ254V-11-02P")
      (footprint "easyedapro:HDR-TH_2P-P2.54-V-M")
      (fields (field (name "Manufacturer") "XFCN(兴飞)"))
      (libsource (lib "easyedapro") (part "PZ254V-11-02P"))
    )
    (comp (ref "H2")
      (value "PZ254V-11-01P")
      (footprint "easyedapro:HDR-TH_1P-P2.54-V-M")
      (fields (field (name "Manufacturer") "XFCN(兴飞)"))
      (libsource (lib "easyedapro") (part "PZ254V-11-01P"))
    )
    (comp (ref "K1")
      (value "SRD-12VDC-SD-C")
      (footprint "easyedapro:RELAY-TH_SRD-XXVDC-SD-C")
      (description "线圈电压:12V;引脚数:5;触点形式:一组转换:1C(单刀双掷-转换);触点容量(电阻负载):-;")
      (fields (field (name "Manufacturer") "松乐"))
      (libsource (lib "easyedapro") (part "SRD-12VDC-SD-C"))
    )
    (comp (ref "LED4")
      (value "19-217/GHC-YR1S2/3T")
      (footprint "easyedapro:LED0603-RD")
      (description "发光颜色:翠绿;二极管配置:-;主波长:520nm~535nm;色温:-;功率:110mW;安装方式:-;")
      (fields (field (name "Manufacturer") "EVERLIGHT(亿光)"))
      (libsource (lib "easyedapro") (part "19-217/GHC-YR1S2/3T"))
    )
    (comp (ref "LED5")
      (value "19-217/GHC-YR1S2/3T")
      (footprint "easyedapro:LED0603-RD")
      (description "发光颜色:翠绿;二极管配置:-;主波长:520nm~535nm;色温:-;功率:110mW;安装方式:-;")
      (fields (field (name "Manufacturer") "EVERLIGHT(亿光)"))
      (libsource (lib "easyedapro") (part "19-217/GHC-YR1S2/3T"))
    )
    (comp (ref "LED6")
      (value "19-217/GHC-YR1S2/3T")
      (footprint "easyedapro:LED0603-RD")
      (description "发光颜色:翠绿;二极管配置:-;主波长:520nm~535nm;色温:-;功率:110mW;安装方式:-;")
      (fields (field (name "Manufacturer") "EVERLIGHT(亿光)"))
      (libsource (lib "easyedapro") (part "19-217/GHC-YR1S2/3T"))
    )
    (comp (ref "LED7")
      (value "19-217/GHC-YR1S2/3T")
      (footprint "easyedapro:LED0603-RD")
      (description "发光颜色:翠绿;二极管配置:-;主波长:520nm~535nm;色温:-;功率:110mW;安装方式:-;")
      (fields (field (name "Manufacturer") "EVERLIGHT(亿光)"))
      (libsource (lib "easyedapro") (part "19-217/GHC-YR1S2/3T"))
    )
    (comp (ref "LED8")
      (value "19-217/GHC-YR1S2/3T")
      (footprint "easyedapro:LED0603-RD")
      (description "发光颜色:翠绿;二极管配置:-;主波长:520nm~535nm;色温:-;功率:110mW;安装方式:-;")
      (fields (field (name "Manufacturer") "EVERLIGHT(亿光)"))
      (libsource (lib "easyedapro") (part "19-217/GHC-YR1S2/3T"))
    )
    (comp (ref "LED9")
      (value "19-217/GHC-YR1S2/3T")
      (footprint "easyedapro:LED0603-RD")
      (description "发光颜色:翠绿;二极管配置:-;主波长:520nm~535nm;色温:-;功率:110mW;安装方式:-;")
      (fields (field (name "Manufacturer") "EVERLIGHT(亿光)"))
      (libsource (lib "easyedapro") (part "19-217/GHC-YR1S2/3T"))
    )
    (comp (ref "LED10")
      (value "19-217/GHC-YR1S2/3T")
      (footprint "easyedapro:LED0603-RD")
      (description "发光颜色:翠绿;二极管配置:-;主波长:520nm~535nm;色温:-;功率:110mW;安装方式:-;")
      (fields (field (name "Manufacturer") "EVERLIGHT(亿光)"))
      (libsource (lib "easyedapro") (part "19-217/GHC-YR1S2/3T"))
    )
    (comp (ref "LED11")
      (value "19-217/GHC-YR1S2/3T")
      (footprint "easyedapro:LED0603-RD")
      (description "发光颜色:翠绿;二极管配置:-;主波长:520nm~535nm;色温:-;功率:110mW;安装方式:-;")
      (fields (field (name "Manufacturer") "EVERLIGHT(亿光)"))
      (libsource (lib "easyedapro") (part "19-217/GHC-YR1S2/3T"))
    )
    (comp (ref "LED12")
      (value "19-217/GHC-YR1S2/3T")
      (footprint "easyedapro:LED0603-RD")
      (description "发光颜色:翠绿;二极管配置:-;主波长:520nm~535nm;色温:-;功率:110mW;安装方式:-;")
      (fields (field (name "Manufacturer") "EVERLIGHT(亿光)"))
      (libsource (lib "easyedapro") (part "19-217/GHC-YR1S2/3T"))
    )
    (comp (ref "Q1")
      (value "SS8050")
      (footprint "easyedapro:SOT-23-3_L2.9-W1.3-P1.90-LS2.4-BR")
      (description "晶体管类型:NPN;集射极击穿电压(Vceo):25V;集电极电流(Ic):1.5A;功率(Pd):300mW;直流电流增益(hFE@Ic,Vce):200@100mA,1V;")
      (fields (field (name "Manufacturer") "CJ(江苏长电/长晶)"))
      (libsource (lib "easyedapro") (part "SS8050_C2150"))
    )
    (comp (ref "Q2")
      (value "SS8050")
      (footprint "easyedapro:SOT-23-3_L2.9-W1.3-P1.90-LS2.4-BR")
      (description "晶体管类型:NPN;集射极击穿电压(Vceo):25V;集电极电流(Ic):1.5A;功率(Pd):300mW;直流电流增益(hFE@Ic,Vce):200@100mA,1V;")
      (fields (field (name "Manufacturer") "CJ(江苏长电/长晶)"))
      (libsource (lib "easyedapro") (part "SS8050_C2150"))
    )
    (comp (ref "Q3")
      (value "SS8050")
      (footprint "easyedapro:SOT-23-3_L2.9-W1.3-P1.90-LS2.4-BR")
      (description "晶体管类型:NPN;集射极击穿电压(Vceo):25V;集电极电流(Ic):1.5A;功率(Pd):300mW;直流电流增益(hFE@Ic,Vce):200@100mA,1V;")
      (fields (field (name "Manufacturer") "CJ(江苏长电/长晶)"))
      (libsource (lib "easyedapro") (part "SS8050_C2150"))
    )
    (comp (ref "Q4")
      (value "SS8050")
      (footprint "easyedapro:SOT-23-3_L2.9-W1.3-P1.90-LS2.4-BR")
      (description "晶体管类型:NPN;集射极击穿电压(Vceo):25V;集电极电流(Ic):1.5A;功率(Pd):300mW;直流电流增益(hFE@Ic,Vce):200@100mA,1V;")
      (fields (field (name "Manufacturer") "CJ(江苏长电/长晶)"))
      (libsource (lib "easyedapro") (part "SS8050_C2150"))
    )
    (comp (ref "Q5")
      (value "SS8050")
      (footprint "easyedapro:SOT-23-3_L2.9-W1.3-P1.90-LS2.4-BR")
      (description "晶体管类型:NPN;集射极击穿电压(Vceo):25V;集电极电流(Ic):1.5A;功率(Pd):300mW;直流电流增益(hFE@Ic,Vce):200@100mA,1V;")
      (fields (field (name "Manufacturer") "CJ(江苏长电/长晶)"))
      (libsource (lib "easyedapro") (part "SS8050_C2150"))
    )
    (comp (ref "Q6")
      (value "SS8050")
      (footprint "easyedapro:SOT-23-3_L2.9-W1.3-P1.90-LS2.4-BR")
      (description "晶体管类型:NPN;集射极击穿电压(Vceo):25V;集电极电流(Ic):1.5A;功率(Pd):300mW;直流电流增益(hFE@Ic,Vce):200@100mA,1V;")
      (fields (field (name "Manufacturer") "CJ(江苏长电/长晶)"))
      (libsource (lib "easyedapro") (part "SS8050_C2150"))
    )
    (comp (ref "Q7")
      (value "SS8050")
      (footprint "easyedapro:SOT-23-3_L2.9-W1.3-P1.90-LS2.4-BR")
      (description "晶体管类型:NPN;集射极击穿电压(Vceo):25V;集电极电流(Ic):1.5A;功率(Pd):300mW;直流电流增益(hFE@Ic,Vce):200@100mA,1V;")
      (fields (field (name "Manufacturer") "CJ(江苏长电/长晶)"))
      (libsource (lib "easyedapro") (part "SS8050_C2150"))
    )
    (comp (ref "Q8")
      (value "SS8050")
      (footprint "easyedapro:SOT-23-3_L2.9-W1.3-P1.90-LS2.4-BR")
      (description "晶体管类型:NPN;集射极击穿电压(Vceo):25V;集电极电流(Ic):1.5A;功率(Pd):300mW;直流电流增益(hFE@Ic,Vce):200@100mA,1V;")
      (fields (field (name "Manufacturer") "CJ(江苏长电/长晶)"))
      (libsource (lib "easyedapro") (part "SS8050_C2150"))
    )
    (comp (ref "Q9")
      (value "SS8050")
      (footprint "easyedapro:SOT-23-3_L2.9-W1.3-P1.90-LS2.4-BR")
      (description "晶体管类型:NPN;集射极击穿电压(Vceo):25V;集电极电流(Ic):1.5A;功率(Pd):300mW;直流电流增益(hFE@Ic,Vce):200@100mA,1V;")
      (fields (field (name "Manufacturer") "CJ(江苏长电/长晶)"))
      (libsource (lib "easyedapro") (part "SS8050_C2150"))
    )
    (comp (ref "R5")
      (value "10kΩ")
      (footprint "easyedapro:R0603")
      (description "电阻类型:厚膜电阻;阻值:10kΩ;精度:±1%;功率:100mW;")
      (fields
        (field (name "Manufacturer Part") "0603WAF1002T5E")
        (field (name "Manufacturer") "UNI-ROYAL(厚声)")
      )
      (libsource (lib "easyedapro") (part "0603WAF1002T5E"))
    )
    (comp (ref "R6")
      (value "10kΩ")
      (footprint "easyedapro:R0603")
      (description "电阻类型:厚膜电阻;阻值:10kΩ;精度:±1%;功率:100mW;")
      (fields
        (field (name "Manufacturer Part") "0603WAF1002T5E")
        (field (name "Manufacturer") "UNI-ROYAL(厚声)")
      )
      (libsource (lib "easyedapro") (part "0603WAF1002T5E"))
    )
    (comp (ref "R7")
      (value "10kΩ")
      (footprint "easyedapro:R0603")
      (description "电阻类型:厚膜电阻;阻值:10kΩ;精度:±1%;功率:100mW;")
      (fields
        (field (name "Manufacturer Part") "0603WAF1002T5E")
        (field (name "Manufacturer") "UNI-ROYAL(厚声)")
      )
      (libsource (lib "easyedapro") (part "0603WAF1002T5E"))
    )
    (comp (ref "R8")
      (value "10kΩ")
      (footprint "easyedapro:R0603")
      (description "电阻类型:厚膜电阻;阻值:10kΩ;精度:±1%;功率:100mW;")
      (fields
        (field (name "Manufacturer Part") "0603WAF1002T5E")
        (field (name "Manufacturer") "UNI-ROYAL(厚声)")
      )
      (libsource (lib "easyedapro") (part "0603WAF1002T5E"))
    )
    (comp (ref "R9")
      (value "10kΩ")
      (footprint "easyedapro:R0603")
      (description "电阻类型:厚膜电阻;阻值:10kΩ;精度:±1%;功率:100mW;")
      (fields
        (field (name "Manufacturer Part") "0603WAF1002T5E")
        (field (name "Manufacturer") "UNI-ROYAL(厚声)")
      )
      (libsource (lib "easyedapro") (part "0603WAF1002T5E"))
    )
    (comp (ref "R10")
      (value "10kΩ")
      (footprint "easyedapro:R0603")
      (description "电阻类型:厚膜电阻;阻值:10kΩ;精度:±1%;功率:100mW;")
      (fields
        (field (name "Manufacturer Part") "0603WAF1002T5E")
        (field (name "Manufacturer") "UNI-ROYAL(厚声)")
      )
      (libsource (lib "easyedapro") (part "0603WAF1002T5E"))
    )
    (comp (ref "R11")
      (value "10kΩ")
      (footprint "easyedapro:R0603")
      (description "电阻类型:厚膜电阻;阻值:10kΩ;精度:±1%;功率:100mW;")
      (fields
        (field (name "Manufacturer Part") "0603WAF1002T5E")
        (field (name "Manufacturer") "UNI-ROYAL(厚声)")
      )
      (libsource (lib "easyedapro") (part "0603WAF1002T5E"))
    )
    (comp (ref "R12")
      (value "10kΩ")
      (footprint "easyedapro:R0603")
      (description "电阻类型:厚膜电阻;阻值:10kΩ;精度:±1%;功率:100mW;")
      (fields
        (field (name "Manufacturer Part") "0603WAF1002T5E")
        (field (name "Manufacturer") "UNI-ROYAL(厚声)")
      )
      (libsource (lib "easyedapro") (part "0603WAF1002T5E"))
    )
    (comp (ref "R13")
      (value "10kΩ")
      (footprint "easyedapro:R0603")
      (description "电阻类型:厚膜电阻;阻值:10kΩ;精度:±1%;功率:100mW;")
      (fields
        (field (name "Manufacturer Part") "0603WAF1002T5E")
        (field (name "Manufacturer") "UNI-ROYAL(厚声)")
      )
      (libsource (lib "easyedapro") (part "0603WAF1002T5E"))
    )
    (comp (ref "R14")
      (value "0Ω")
      (footprint "easyedapro:R0603")
      (description "电阻类型:厚膜电阻;阻值:0Ω;精度:±1%;功率:100mW;")
      (fields
        (field (name "Manufacturer Part") "0603WAF0000T5E")
        (field (name "Manufacturer") "UNI-ROYAL(厚声)")
      )
      (libsource (lib "easyedapro") (part "0603WAF0000T5E"))
    )
    (comp (ref "R15")
      (value "100Ω")
      (footprint "easyedapro:R0603")
      (description "电阻类型:厚膜电阻;阻值:100Ω;精度:±1%;功率:100mW;")
      (fields (field (name "Manufacturer Part") "RC0603FR-07100RL") (field (name "Manufacturer") "YAGEO(国巨)"))
      (libsource (lib "easyedapro") (part "RC0603FR-07100RL"))
    )
    (comp (ref "RELAY1")
      (value "SRD-12VDC-SL-C")
      (footprint "easyedapro:RELAY-TH_SRD-XXVDC-XL-C")
      (description "线圈电压:12V;引脚数:5;触点形式:一组转换:1C(单刀双掷-转换);触点容量(电阻负载):-;")
      (fields (field (name "Manufacturer") "松乐"))
      (libsource (lib "easyedapro") (part "SRD-12VDC-SL-C"))
    )
    (comp (ref "RELAY2")
      (value "SRD-12VDC-SL-C")
      (footprint "easyedapro:RELAY-TH_SRD-XXVDC-XL-C")
      (description "线圈电压:12V;引脚数:5;触点形式:一组转换:1C(单刀双掷-转换);触点容量(电阻负载):-;")
      (fields (field (name "Manufacturer") "松乐"))
      (libsource (lib "easyedapro") (part "SRD-12VDC-SL-C"))
    )
    (comp (ref "RELAY3")
      (value "SRD-12VDC-SL-C")
      (footprint "easyedapro:RELAY-TH_SRD-XXVDC-XL-C")
      (description "线圈电压:12V;引脚数:5;触点形式:一组转换:1C(单刀双掷-转换);触点容量(电阻负载):-;")
      (fields (field (name "Manufacturer") "松乐"))
      (libsource (lib "easyedapro") (part "SRD-12VDC-SL-C"))
    )
    (comp (ref "RELAY4")
      (value "SRD-12VDC-SL-C")
      (footprint "easyedapro:RELAY-TH_SRD-XXVDC-XL-C")
      (description "线圈电压:12V;引脚数:5;触点形式:一组转换:1C(单刀双掷-转换);触点容量(电阻负载):-;")
      (fields (field (name "Manufacturer") "松乐"))
      (libsource (lib "easyedapro") (part "SRD-12VDC-SL-C"))
    )
    (comp (ref "RELAY5")
      (value "SRD-12VDC-SL-C")
      (footprint "easyedapro:RELAY-TH_SRD-XXVDC-XL-C")
      (description "线圈电压:12V;引脚数:5;触点形式:一组转换:1C(单刀双掷-转换);触点容量(电阻负载):-;")
      (fields (field (name "Manufacturer") "松乐"))
      (libsource (lib "easyedapro") (part "SRD-12VDC-SL-C"))
    )
    (comp (ref "RELAY6")
      (value "SRD-12VDC-SL-C")
      (footprint "easyedapro:RELAY-TH_SRD-XXVDC-XL-C")
      (description "线圈电压:12V;引脚数:5;触点形式:一组转换:1C(单刀双掷-转换);触点容量(电阻负载):-;")
      (fields (field (name "Manufacturer") "松乐"))
      (libsource (lib "easyedapro") (part "SRD-12VDC-SL-C"))
    )
    (comp (ref "RELAY7")
      (value "SRD-12VDC-SL-C")
      (footprint "easyedapro:RELAY-TH_SRD-XXVDC-XL-C")
      (description "线圈电压:12V;引脚数:5;触点形式:一组转换:1C(单刀双掷-转换);触点容量(电阻负载):-;")
      (fields (field (name "Manufacturer") "松乐"))
      (libsource (lib "easyedapro") (part "SRD-12VDC-SL-C"))
    )
    (comp (ref "RELAY8")
      (value "SRD-12VDC-SL-C")
      (footprint "easyedapro:RELAY-TH_SRD-XXVDC-XL-C")
      (description "线圈电压:12V;引脚数:5;触点形式:一组转换:1C(单刀双掷-转换);触点容量(电阻负载):-;")
      (fields (field (name "Manufacturer") "松乐"))
      (libsource (lib "easyedapro") (part "SRD-12VDC-SL-C"))
    )
    (comp (ref "RELAY9")
      (value "SRD-12VDC-SL-C")
      (footprint "easyedapro:RELAY-TH_SRD-XXVDC-XL-C")
      (description "线圈电压:12V;引脚数:5;触点形式:一组转换:1C(单刀双掷-转换);触点容量(电阻负载):-;")
      (fields (field (name "Manufacturer") "松乐"))
      (libsource (lib "easyedapro") (part "SRD-12VDC-SL-C"))
    )
    (comp (ref "U21")
      (value "X5511FV-01-C30D97-0970")
      (footprint "easyedapro:HDR-TH_1P-V-F-1")
      (fields (field (name "Manufacturer") "XKB Connectivity(中国星坤)"))
      (libsource (lib "easyedapro") (part "X5511FV-01-C30D97-0970"))
    )
    (comp (ref "U27")
      (value "X5511FV-01-C30D97-0970")
      (footprint "easyedapro:HDR-TH_1P-V-F-1")
      (fields (field (name "Manufacturer") "XKB Connectivity(中国星坤)"))
      (libsource (lib "easyedapro") (part "X5511FV-01-C30D97-0970"))
    )
    (comp (ref "U28")
      (value "X5511FV-01-C30D97-0970")
      (footprint "easyedapro:HDR-TH_1P-V-F-1")
      (fields (field (name "Manufacturer") "XKB Connectivity(中国星坤)"))
      (libsource (lib "easyedapro") (part "X5511FV-01-C30D97-0970"))
    )
    (comp (ref "U29")
      (value "X5511FV-01-C30D97-0970")
      (footprint "easyedapro:HDR-TH_1P-V-F-1")
      (fields (field (name "Manufacturer") "XKB Connectivity(中国星坤)"))
      (libsource (lib "easyedapro") (part "X5511FV-01-C30D97-0970"))
    )
    (comp (ref "U30")
      (value "X5511FV-01-C30D97-0970")
      (footprint "easyedapro:HDR-TH_1P-V-F-1")
      (fields (field (name "Manufacturer") "XKB Connectivity(中国星坤)"))
      (libsource (lib "easyedapro") (part "X5511FV-01-C30D97-0970"))
    )
    (comp (ref "U31")
      (value "X5511FV-01-C30D97-0970")
      (footprint "easyedapro:HDR-TH_1P-V-F-1")
      (fields (field (name "Manufacturer") "XKB Connectivity(中国星坤)"))
      (libsource (lib "easyedapro") (part "X5511FV-01-C30D97-0970"))
    )
    (comp (ref "U32")
      (value "X5511FV-01-C30D97-0970")
      (footprint "easyedapro:HDR-TH_1P-V-F-1")
      (fields (field (name "Manufacturer") "XKB Connectivity(中国星坤)"))
      (libsource (lib "easyedapro") (part "X5511FV-01-C30D97-0970"))
    )
    (comp (ref "U33")
      (value "X5511FV-01-C30D97-0970")
      (footprint "easyedapro:HDR-TH_1P-V-F-1")
      (fields (field (name "Manufacturer") "XKB Connectivity(中国星坤)"))
      (libsource (lib "easyedapro") (part "X5511FV-01-C30D97-0970"))
    )
    (comp (ref "U34")
      (value "X5511FV-01-C30D97-0970")
      (footprint "easyedapro:HDR-TH_1P-V-F-1")
      (fields (field (name "Manufacturer") "XKB Connectivity(中国星坤)"))
      (libsource (lib "easyedapro") (part "X5511FV-01-C30D97-0970"))
    )
    (comp (ref "U35")
      (value "X5511FV-01-C30D97-0970")
      (footprint "easyedapro:HDR-TH_1P-V-F-1")
      (fields (field (name "Manufacturer") "XKB Connectivity(中国星坤)"))
      (libsource (lib "easyedapro") (part "X5511FV-01-C30D97-0970"))
    )
    (comp (ref "U36")
      (value "X5511FV-01-C30D97-0970")
      (footprint "easyedapro:HDR-TH_1P-V-F-1")
      (fields (field (name "Manufacturer") "XKB Connectivity(中国星坤)"))
      (libsource (lib "easyedapro") (part "X5511FV-01-C30D97-0970"))
    )
    (comp (ref "U37")
      (value "X5511FV-01-C30D97-0970")
      (footprint "easyedapro:HDR-TH_1P-V-F-1")
      (fields (field (name "Manufacturer") "XKB Connectivity(中国星坤)"))
      (libsource (lib "easyedapro") (part "X5511FV-01-C30D97-0970"))
    )
    (comp (ref "U38")
      (value "RH-5000")
      (footprint "easyedapro:TEST-TH_BD2.54-P1.4_RED")
      (description "100x80mm")
      (fields (field (name "Manufacturer") "荣和"))
      (libsource (lib "easyedapro") (part "RH-5000"))
    )
    (comp (ref "U39")
      (value "RH-5000")
      (footprint "easyedapro:TEST-TH_BD2.54-P1.4_RED")
      (description "100x80mm")
      (fields (field (name "Manufacturer") "荣和"))
      (libsource (lib "easyedapro") (part "RH-5000"))
    )
  )
  (nets
    (net (code "1") (name "DAC_OUT") (class "Default")
      (node (ref "U5") (pin "1") (pinfunction "VOUT_1") (pintype "input"))
      (node (ref "U7") (pin "5") (pinfunction "IN_B+_5") (pintype "unspecified"))
    )
    (net (code "2") (name "DC_5V") (class "Default")
      (node (ref "H1") (pin "2") (pinfunction "2_2") (pintype "input"))
      (node (ref "P1") (pin "1") (pinfunction "1_1") (pintype "unspecified"))
      (node (ref "R15") (pin "1") (pinfunction "1_1") (pintype "input"))
    )
    (net (code "3") (name "DC_12V") (class "Default")
      (node (ref "C1") (pin "1") (pinfunction "1_1") (pintype "input"))
      (node (ref "C16") (pin "1") (pinfunction "1_1") (pintype "input"))
      (node (ref "C17") (pin "1") (pinfunction "1_1") (pintype "input"))
      (node (ref "C2") (pin "2") (pinfunction "2_2") (pintype "input"))
      (node (ref "C3") (pin "2") (pinfunction "2_2") (pintype "input"))
      (node (ref "D1") (pin "2") (pinfunction "K_2") (pintype "input"))
      (node (ref "D10") (pin "1") (pinfunction "K_1") (pintype "unspecified"))
      (node (ref "D11") (pin "1") (pinfunction "K_1") (pintype "unspecified"))
      (node (ref "D12") (pin "1") (pinfunction "K_1") (pintype "unspecified"))
      (node (ref "D4") (pin "1") (pinfunction "K_1") (pintype "unspecified"))
      (node (ref "D5") (pin "1") (pinfunction "K_1") (pintype "unspecified"))
      (node (ref "D6") (pin "1") (pinfunction "K_1") (pintype "unspecified"))
      (node (ref "D7") (pin "1") (pinfunction "K_1") (pintype "unspecified"))
      (node (ref "D8") (pin "1") (pinfunction "K_1") (pintype "unspecified"))
      (node (ref "D9") (pin "1") (pinfunction "K_1") (pintype "unspecified"))
      (node (ref "RELAY1") (pin "1") (pinfunction "1_1") (pintype "input"))
      (node (ref "RELAY2") (pin "1") (pinfunction "1_1") (pintype "input"))
      (node (ref "RELAY3") (pin "1") (pinfunction "1_1") (pintype "input"))
      (node (ref "RELAY4") (pin "1") (pinfunction "1_1") (pintype "input"))
      (node (ref "RELAY5") (pin "1") (pinfunction "1_1") (pintype "input"))
      (node (ref "RELAY6") (pin "1") (pinfunction "1_1") (pintype "input"))
      (node (ref "RELAY7") (pin "1") (pinfunction "1_1") (pintype "input"))
      (node (ref "RELAY8") (pin "1") (pinfunction "1_1") (pintype "input"))
      (node (ref "RELAY9") (pin "1") (pinfunction "1_1") (pintype "input"))
      (node (ref "U3") (pin "1") (pinfunction "IN_1") (pintype "input"))
      (node (ref "U8") (pin "2") (pinfunction "VIN_2") (pintype "input"))
    )
    (net (code "4") (name "DUT_TX") (class "Default")
      (node (ref "RF2") (pin "5") (pinfunction "5_5") (pintype "input"))
      (node (ref "U1") (pin "31") (pinfunction "PA10/CMP1_OUT/TIM1_CH3/UART1_RX/I2C1_SDA/TIM7_BKIN_31") (pintype "input"))
    )
    (net (code "5") (name "DUT_VCC_DAC") (class "Default")
      (node (ref "C14") (pin "2") (pinfunction "2_2") (pintype "input"))
      (node (ref "H3") (pin "1") (pinfunction "1_1") (pintype "input"))
      (node (ref "R4") (pin "2") (pinfunction "2_2") (pintype "input"))
      (node (ref "U40") (pin "1") (pinfunction "1_1") (pintype "input"))
    )
    (net (code "6") (name "DUT_VCC_RLY") (class "Default")
      (node (ref "H2") (pin "1") (pinfunction "1_1") (pintype "input"))
      (node (ref "RELAY9") (pin "2") (pinfunction "2_2") (pintype "input"))
      (node (ref "U38") (pin "1") (pinfunction "1_1") (pintype "input"))
    )
    (net (code "7") (name "GET_DUT_SIGNAL") (class "Default")
      (node (ref "RF1") (pin "5") (pinfunction "5_5") (pintype "input"))
      (node (ref "U1") (pin "29") (pinfunction "PA8/MCO/TIM1_CH1/CMP2_OUT_29") (pintype "input"))
    )
    (net (code "8") (name "GND") (class "Default")
      (node (ref "C1") (pin "2") (pinfunction "2_2") (pintype "input"))
      (node (ref "C10") (pin "1") (pinfunction "1_1") (pintype "input"))
      (node (ref "C11") (pin "1") (pinfunction "1_1") (pintype "input"))
      (node (ref "C12") (pin "2") (pinfunction "2_2") (pintype "input"))
      (node (ref "C13") (pin "2") (pinfunction "2_2") (pintype "input"))
      (node (ref "C14") (pin "1") (pinfunction "1_1") (pintype "input"))
      (node (ref "C15") (pin "1") (pinfunction "1_1") (pintype "input"))
      (node (ref "C16") (pin "2") (pinfunction "2_2") (pintype "input"))
      (node (ref "C17") (pin "2") (pinfunction "2_2") (pintype "input"))
      (node (ref "C18") (pin "2") (pinfunction "2_2") (pintype "input"))
      (node (ref "C19") (pin "2") (pinfunction "2_2") (pintype "input"))
      (node (ref "C2") (pin "1") (pinfunction "1_1") (pintype "input"))
      (node (ref "C20") (pin "2") (pinfunction "2_2") (pintype "input"))
      (node (ref "C21") (pin "2") (pinfunction "2_2") (pintype "input"))
      (node (ref "C22") (pin "1") (pinfunction "1_1") (pintype "input"))
      (node (ref "C23") (pin "1") (pinfunction "1_1") (pintype "input"))
      (node (ref "C24") (pin "1") (pinfunction "1_1") (pintype "input"))
      (node (ref "C25") (pin "1") (pinfunction "1_1") (pintype "input"))
      (node (ref "C3") (pin "1") (pinfunction "1_1") (pintype "input"))
      (node (ref "C4") (pin "1") (pinfunction "1_1") (pintype "input"))
      (node (ref "C5") (pin "1") (pinfunction "1_1") (pintype "input"))
      (node (ref "C6") (pin "1") (pinfunction "1_1") (pintype "input"))
      (node (ref "C7") (pin "2") (pinfunction "2_2") (pintype "input"))
      (node (ref "C8") (pin "2") (pinfunction "2_2") (pintype "input"))
      (node (ref "C9") (pin "2") (pinfunction "2_2") (pintype "input"))
      (node (ref "D2") (pin "2") (pinfunction "A_2") (pintype "unspecified"))
      (node (ref "D3") (pin "2") (pinfunction "A_2") (pintype "input"))
      (node (ref "DC1") (pin "2") (pinfunction "2_2") (pintype "input"))
      (node (ref "DC1") (pin "3") (pinfunction "3_3") (pintype "input"))
      (node (ref "J2") (pin "1") (pinfunction "1_1") (pintype "input"))
      (node (ref "J3") (pin "1") (pinfunction "1_1") (pintype "input"))
      (node (ref "J4") (pin "1") (pinfunction "1_1") (pintype "input"))
      (node (ref "J5") (pin "1") (pinfunction "1_1") (pintype "input"))
      (node (ref "LED13") (pin "1") (pinfunction "C_1") (pintype "input"))
      (node (ref "P1") (pin "2") (pinfunction "2_2") (pintype "unspecified"))
      (node (ref "Q1") (pin "2") (pinfunction "E_2") (pintype "input"))
      (node (ref "Q2") (pin "2") (pinfunction "E_2") (pintype "input"))
      (node (ref "Q3") (pin "2") (pinfunction "E_2") (pintype "input"))
      (node (ref "Q4") (pin "2") (pinfunction "E_2") (pintype "input"))
      (node (ref "Q5") (pin "2") (pinfunction "E_2") (pintype "input"))
      (node (ref "Q6") (pin "2") (pinfunction "E_2") (pintype "input"))
      (node (ref "Q7") (pin "2") (pinfunction "E_2") (pintype "input"))
      (node (ref "Q8") (pin "2") (pinfunction "E_2") (pintype "input"))
      (node (ref "Q9") (pin "2") (pinfunction "E_2") (pintype "input"))
      (node (ref "R14") (pin "1") (pinfunction "1_1") (pintype "input"))
      (node (ref "RF1") (pin "1") (pinfunction "1_1") (pintype "input"))
      (node (ref "RF1") (pin "2") (pinfunction "2_2") (pintype "input"))
      (node (ref "RF1") (pin "3") (pinfunction "3_3") (pintype "input"))
      (node (ref "RF1") (pin "4") (pinfunction "4_4") (pintype "input"))
      (node (ref "RF2") (pin "1") (pinfunction "1_1") (pintype "input"))
      (node (ref "RF2") (pin "2") (pinfunction "2_2") (pintype "input"))
      (node (ref "RF2") (pin "3") (pinfunction "3_3") (pintype "input"))
      (node (ref "RF2") (pin "4") (pinfunction "4_4") (pintype "input"))
      (node (ref "U1") (pin "23") (pinfunction "VSS_23") (pintype "input"))
      (node (ref "U1") (pin "47") (pinfunction "VSS_47") (pintype "input"))
      (node (ref "U1") (pin "8") (pinfunction "VSSA_8") (pintype "input"))
      (node (ref "U2") (pin "10") (pinfunction "10_10") (pintype "input"))
      (node (ref "U2") (pin "8") (pinfunction "8_8") (pintype "input"))
      (node (ref "U2") (pin "9") (pinfunction "9_9") (pintype "input"))
      (node (ref "U27") (pin "1") (pinfunction "1_1") (pintype "unspecified"))
      (node (ref "U28") (pin "1") (pinfunction "1_1") (pintype "unspecified"))
      (node (ref "U3") (pin "4") (pinfunction "GND_4") (pintype "input"))
      (node (ref "U30") (pin "1") (pinfunction "1_1") (pintype "unspecified"))
      (node (ref "U32") (pin "1") (pinfunction "1_1") (pintype "unspecified"))
      (node (ref "U34") (pin "1") (pinfunction "1_1") (pintype "unspecified"))
      (node (ref "U36") (pin "1") (pinfunction "1_1") (pintype "unspecified"))
      (node (ref "U39") (pin "1") (pinfunction "1_1") (pintype "input"))
      (node (ref "U4") (pin "1") (pinfunction "GND_1") (pintype "unspecified"))
      (node (ref "U5") (pin "2") (pinfunction "AGND_2") (pintype "input"))
      (node (ref "U5") (pin "7") (pinfunction "DGND_7") (pintype "input"))
      (node (ref "U7") (pin "4") (pinfunction "V-_4") (pintype "unspecified"))
      (node (ref "U8") (pin "4") (pinfunction "GND_4") (pintype "input"))
      (node (ref "X1") (pin "2") (pinfunction "2_2") (pintype "input"))
      (node (ref "X1") (pin "4") (pinfunction "4_4") (pintype "input"))
    )
    (net (code "9") (name "LDO_5V") (class "Default")
      (node (ref "C12") (pin "1") (pinfunction "1_1") (pintype "input"))
      (node (ref "C13") (pin "1") (pinfunction "1_1") (pintype "input"))
      (node (ref "C20") (pin "1") (pinfunction "1_1") (pintype "input"))
      (node (ref "C21") (pin "1") (pinfunction "1_1") (pintype "input"))
      (node (ref "C22") (pin "2") (pinfunction "2_2") (pintype "input"))
      (node (ref "C23") (pin "2") (pinfunction "2_2") (pintype "input"))
      (node (ref "C24") (pin "2") (pinfunction "2_2") (pintype "input"))
      (node (ref "C25") (pin "2") (pinfunction "2_2") (pintype "input"))
      (node (ref "C4") (pin "2") (pinfunction "2_2") (pintype "input"))
      (node (ref "C7") (pin "1") (pinfunction "1_1") (pintype "input"))
      (node (ref "C8") (pin "1") (pinfunction "1_1") (pintype "input"))
      (node (ref "D13") (pin "2") (pinfunction "A_2") (pintype "input"))
      (node (ref "LED1") (pin "2") (pinfunction "A_2") (pintype "input"))
      (node (ref "LED2") (pin "2") (pinfunction "A_2") (pintype "input"))
      (node (ref "LED3") (pin "2") (pinfunction "A_2") (pintype "input"))
      (node (ref "R16") (pin "2") (pinfunction "2_2") (pintype "input"))
      (node (ref "U1") (pin "1") (pinfunction "VDD_1") (pintype "input"))
      (node (ref "U1") (pin "24") (pinfunction "VDD_24") (pintype "input"))
      (node (ref "U1") (pin "48") (pinfunction "VDD_48") (pintype "input"))
      (node (ref "U1") (pin "9") (pinfunction "VDDA_9") (pintype "input"))
      (node (ref "U2") (pin "1") (pinfunction "1_1") (pintype "input"))
      (node (ref "U3") (pin "3") (pinfunction "OUT_3") (pintype "input"))
      (node (ref "U4") (pin "16") (pinfunction "VCC_16") (pintype "unspecified"))
      (node (ref "U5") (pin "8") (pinfunction "VDD_8") (pintype "input"))
      (node (ref "U7") (pin "8") (pinfunction "V+_8") (pintype "unspecified"))
    )
    (net (code "10") (name "LED_BLUE") (class "Default")
      (node (ref "R2") (pin "1") (pinfunction "1_1") (pintype "input"))
      (node (ref "U1") (pin "3") (pinfunction "PC14_3") (pintype "input"))
    )
    (net (code "11") (name "LED_GREEN") (class "Default")
      (node (ref "R3") (pin "1") (pinfunction "1_1") (pintype "input"))
      (node (ref "U1") (pin "4") (pinfunction "PC15_4") (pintype "input"))
    )
    (net (code "12") (name "LED_RED") (class "Default")
      (node (ref "R1") (pin "1") (pinfunction "1_1") (pintype "input"))
      (node (ref "U1") (pin "2") (pinfunction "PC13_2") (pintype "input"))
    )
    (net (code "13") (name "MCO") (class "Default")
      (node (ref "U1") (pin "30") (pinfunction "PA9/CMP0_OUT/TIM1_CH2/UART1_TX/I2C1_SCL/MCO/TIM5_BKIN_30") (pintype "input"))
      (node (ref "U2") (pin "7") (pinfunction "7_7") (pintype "input"))
    )
    (net (code "14") (name "Net-(D1-A)") (class "Default")
      (node (ref "D1") (pin "1") (pinfunction "A_1") (pintype "input"))
      (node (ref "DC1") (pin "4") (pinfunction "4_4") (pintype "input"))
    )
    (net (code "15") (name "Net-(D3-K)") (class "Default")
      (node (ref "D3") (pin "1") (pinfunction "K_1") (pintype "input"))
      (node (ref "USB1") (pin "4") (pinfunction "GND_4") (pintype "input"))
      (node (ref "USB1") (pin "5") (pinfunction "GND_5") (pintype "input"))
      (node (ref "USB1") (pin "6") (pinfunction "GND_6") (pintype "input"))
    )
    (net (code "16") (name "Net-(D4-A)") (class "Default")
      (node (ref "D4") (pin "2") (pinfunction "A_2") (pintype "unspecified"))
      (node (ref "Q1") (pin "3") (pinfunction "C_3") (pintype "input"))
      (node (ref "RELAY1") (pin "4") (pinfunction "4_4") (pintype "input"))
    )
    (net (code "17") (name "Net-(D5-A)") (class "Default")
      (node (ref "D5") (pin "2") (pinfunction "A_2") (pintype "unspecified"))
      (node (ref "Q2") (pin "3") (pinfunction "C_3") (pintype "input"))
      (node (ref "RELAY2") (pin "4") (pinfunction "4_4") (pintype "input"))
    )
    (net (code "18") (name "Net-(D6-A)") (class "Default")
      (node (ref "D6") (pin "2") (pinfunction "A_2") (pintype "unspecified"))
      (node (ref "Q3") (pin "3") (pinfunction "C_3") (pintype "input"))
      (node (ref "RELAY3") (pin "4") (pinfunction "4_4") (pintype "input"))
    )
    (net (code "19") (name "Net-(D7-A)") (class "Default")
      (node (ref "D7") (pin "2") (pinfunction "A_2") (pintype "unspecified"))
      (node (ref "Q4") (pin "3") (pinfunction "C_3") (pintype "input"))
      (node (ref "RELAY4") (pin "4") (pinfunction "4_4") (pintype "input"))
    )
    (net (code "20") (name "Net-(D8-A)") (class "Default")
      (node (ref "D8") (pin "2") (pinfunction "A_2") (pintype "unspecified"))
      (node (ref "Q5") (pin "3") (pinfunction "C_3") (pintype "input"))
      (node (ref "RELAY5") (pin "4") (pinfunction "4_4") (pintype "input"))
    )
    (net (code "21") (name "Net-(D9-A)") (class "Default")
      (node (ref "D9") (pin "2") (pinfunction "A_2") (pintype "unspecified"))
      (node (ref "Q6") (pin "3") (pinfunction "C_3") (pintype "input"))
      (node (ref "RELAY6") (pin "4") (pinfunction "4_4") (pintype "input"))
    )
    (net (code "22") (name "Net-(D10-A)") (class "Default")
      (node (ref "D10") (pin "2") (pinfunction "A_2") (pintype "unspecified"))
      (node (ref "Q7") (pin "3") (pinfunction "C_3") (pintype "input"))
      (node (ref "RELAY7") (pin "4") (pinfunction "4_4") (pintype "input"))
    )
    (net (code "23") (name "Net-(D11-A)") (class "Default")
      (node (ref "D11") (pin "2") (pinfunction "A_2") (pintype "unspecified"))
      (node (ref "Q8") (pin "3") (pinfunction "C_3") (pintype "input"))
      (node (ref "RELAY8") (pin "4") (pinfunction "4_4") (pintype "input"))
    )
    (net (code "24") (name "Net-(D12-A)") (class "Default")
      (node (ref "D12") (pin "2") (pinfunction "A_2") (pintype "unspecified"))
      (node (ref "Q9") (pin "3") (pinfunction "C_3") (pintype "input"))
      (node (ref "RELAY9") (pin "4") (pinfunction "4_4") (pintype "input"))
    )
    (net (code "25") (name "Net-(D13-K)") (class "Default")
      (node (ref "D13") (pin "1") (pinfunction "K_1") (pintype "input"))
      (node (ref "D2") (pin "1") (pinfunction "K_1") (pintype "unspecified"))
      (node (ref "USB1") (pin "1") (pinfunction "VBUS_1") (pintype "input"))
    )
    (net (code "26") (name "Net-(H1-Pad1)") (class "Default")
      (node (ref "H1") (pin "1") (pinfunction "1_1") (pintype "input"))
      (node (ref "R15") (pin "2") (pinfunction "2_2") (pintype "input"))
      (node (ref "RELAY1") (pin "5") (pinfunction "5_5") (pintype "input"))
    )
    (net (code "27") (name "Net-(LED1-K)") (class "Default")
      (node (ref "LED1") (pin "1") (pinfunction "K_1") (pintype "input"))
      (node (ref "R1") (pin "2") (pinfunction "2_2") (pintype "input"))
    )
    (net (code "28") (name "Net-(LED2-C)") (class "Default")
      (node (ref "LED2") (pin "1") (pinfunction "C_1") (pintype "input"))
      (node (ref "R2") (pin "2") (pinfunction "2_2") (pintype "input"))
    )
    (net (code "29") (name "Net-(LED3-C)") (class "Default")
      (node (ref "LED3") (pin "1") (pinfunction "C_1") (pintype "input"))
      (node (ref "R3") (pin "2") (pinfunction "2_2") (pintype "input"))
    )
    (net (code "30") (name "Net-(LED4-A)") (class "Default")
      (node (ref "LED4") (pin "2") (pinfunction "A_2") (pintype "input"))
      (node (ref "R5") (pin "2") (pinfunction "2_2") (pintype "input"))
    )
    (net (code "31") (name "Net-(LED4-C)") (class "Default")
      (node (ref "LED4") (pin "1") (pinfunction "C_1") (pintype "input"))
      (node (ref "Q1") (pin "1") (pinfunction "B_1") (pintype "input"))
    )
    (net (code "32") (name "Net-(LED5-A)") (class "Default")
      (node (ref "LED5") (pin "2") (pinfunction "A_2") (pintype "input"))
      (node (ref "R6") (pin "2") (pinfunction "2_2") (pintype "input"))
    )
    (net (code "33") (name "Net-(LED5-C)") (class "Default")
      (node (ref "LED5") (pin "1") (pinfunction "C_1") (pintype "input"))
      (node (ref "Q2") (pin "1") (pinfunction "B_1") (pintype "input"))
    )
    (net (code "34") (name "Net-(LED6-A)") (class "Default")
      (node (ref "LED6") (pin "2") (pinfunction "A_2") (pintype "input"))
      (node (ref "R7") (pin "2") (pinfunction "2_2") (pintype "input"))
    )
    (net (code "35") (name "Net-(LED6-C)") (class "Default")
      (node (ref "LED6") (pin "1") (pinfunction "C_1") (pintype "input"))
      (node (ref "Q3") (pin "1") (pinfunction "B_1") (pintype "input"))
    )
    (net (code "36") (name "Net-(LED7-A)") (class "Default")
      (node (ref "LED7") (pin "2") (pinfunction "A_2") (pintype "input"))
      (node (ref "R8") (pin "2") (pinfunction "2_2") (pintype "input"))
    )
    (net (code "37") (name "Net-(LED7-C)") (class "Default")
      (node (ref "LED7") (pin "1") (pinfunction "C_1") (pintype "input"))
      (node (ref "Q4") (pin "1") (pinfunction "B_1") (pintype "input"))
    )
    (net (code "38") (name "Net-(LED8-A)") (class "Default")
      (node (ref "LED8") (pin "2") (pinfunction "A_2") (pintype "input"))
      (node (ref "R9") (pin "2") (pinfunction "2_2") (pintype "input"))
    )
    (net (code "39") (name "Net-(LED8-C)") (class "Default")
      (node (ref "LED8") (pin "1") (pinfunction "C_1") (pintype "input"))
      (node (ref "Q5") (pin "1") (pinfunction "B_1") (pintype "input"))
    )
    (net (code "40") (name "Net-(LED9-A)") (class "Default")
      (node (ref "LED9") (pin "2") (pinfunction "A_2") (pintype "input"))
      (node (ref "R10") (pin "2") (pinfunction "2_2") (pintype "input"))
    )
    (net (code "41") (name "Net-(LED9-C)") (class "Default")
      (node (ref "LED9") (pin "1") (pinfunction "C_1") (pintype "input"))
      (node (ref "Q6") (pin "1") (pinfunction "B_1") (pintype "input"))
    )
    (net (code "42") (name "Net-(LED10-A)") (class "Default")
      (node (ref "LED10") (pin "2") (pinfunction "A_2") (pintype "input"))
      (node (ref "R11") (pin "2") (pinfunction "2_2") (pintype "input"))
    )
    (net (code "43") (name "Net-(LED10-C)") (class "Default")
      (node (ref "LED10") (pin "1") (pinfunction "C_1") (pintype "input"))
      (node (ref "Q7") (pin "1") (pinfunction "B_1") (pintype "input"))
    )
    (net (code "44") (name "Net-(LED11-A)") (class "Default")
      (node (ref "LED11") (pin "2") (pinfunction "A_2") (pintype "input"))
      (node (ref "R12") (pin "2") (pinfunction "2_2") (pintype "input"))
    )
    (net (code "45") (name "Net-(LED11-C)") (class "Default")
      (node (ref "LED11") (pin "1") (pinfunction "C_1") (pintype "input"))
      (node (ref "Q8") (pin "1") (pinfunction "B_1") (pintype "input"))
    )
    (net (code "46") (name "Net-(LED12-A)") (class "Default")
      (node (ref "LED12") (pin "2") (pinfunction "A_2") (pintype "input"))
      (node (ref "R13") (pin "2") (pinfunction "2_2") (pintype "input"))
    )
    (net (code "47") (name "Net-(LED12-C)") (class "Default")
      (node (ref "LED12") (pin "1") (pinfunction "C_1") (pintype "input"))
      (node (ref "Q9") (pin "1") (pinfunction "B_1") (pintype "input"))
    )
    (net (code "48") (name "Net-(LED13-A)") (class "Default")
      (node (ref "LED13") (pin "2") (pinfunction "A_2") (pintype "input"))
      (node (ref "R16") (pin "1") (pinfunction "1_1") (pintype "input"))
    )
    (net (code "49") (name "Net-(R14-Pad2)") (class "Default")
      (node (ref "R14") (pin "2") (pinfunction "2_2") (pintype "input"))
      (node (ref "RELAY8") (pin "2") (pinfunction "2_2") (pintype "input"))
    )
    (net (code "50") (name "Net-(RELAY1-Pad2)") (class "Default")
      (node (ref "RELAY1") (pin "2") (pinfunction "2_2") (pintype "input"))
      (node (ref "RELAY2") (pin "5") (pinfunction "5_5") (pintype "input"))
      (node (ref "RELAY3") (pin "5") (pinfunction "5_5") (pintype "input"))
      (node (ref "RELAY4") (pin "5") (pinfunction "5_5") (pintype "input"))
      (node (ref "RELAY5") (pin "5") (pinfunction "5_5") (pintype "input"))
      (node (ref "RELAY6") (pin "5") (pinfunction "5_5") (pintype "input"))
      (node (ref "RELAY7") (pin "5") (pinfunction "5_5") (pintype "input"))
      (node (ref "RELAY8") (pin "5") (pinfunction "5_5") (pintype "input"))
      (node (ref "RELAY9") (pin "5") (pinfunction "5_5") (pintype "input"))
    )
    (net (code "51") (name "Net-(RELAY2-Pad2)") (class "Default")
      (node (ref "RELAY2") (pin "2") (pinfunction "2_2") (pintype "input"))
      (node (ref "U21") (pin "1") (pinfunction "1_1") (pintype "unspecified"))
    )
    (net (code "52") (name "Net-(RELAY3-Pad2)") (class "Default")
      (node (ref "RELAY3") (pin "2") (pinfunction "2_2") (pintype "input"))
      (node (ref "U29") (pin "1") (pinfunction "1_1") (pintype "unspecified"))
    )
    (net (code "53") (name "Net-(RELAY4-Pad2)") (class "Default")
      (node (ref "RELAY4") (pin "2") (pinfunction "2_2") (pintype "input"))
      (node (ref "U31") (pin "1") (pinfunction "1_1") (pintype "unspecified"))
    )
    (net (code "54") (name "Net-(RELAY5-Pad2)") (class "Default")
      (node (ref "RELAY5") (pin "2") (pinfunction "2_2") (pintype "input"))
      (node (ref "U33") (pin "1") (pinfunction "1_1") (pintype "unspecified"))
    )
    (net (code "55") (name "Net-(RELAY6-Pad2)") (class "Default")
      (node (ref "RELAY6") (pin "2") (pinfunction "2_2") (pintype "input"))
      (node (ref "U35") (pin "1") (pinfunction "1_1") (pintype "unspecified"))
    )
    (net (code "56") (name "Net-(RELAY7-Pad2)") (class "Default")
      (node (ref "RELAY7") (pin "2") (pinfunction "2_2") (pintype "input"))
      (node (ref "U37") (pin "1") (pinfunction "1_1") (pintype "unspecified"))
    )
    (net (code "57") (name "Net-(U4-V3)") (class "Default")
      (node (ref "C9") (pin "1") (pinfunction "1_1") (pintype "input"))
      (node (ref "U4") (pin "4") (pinfunction "V3_4") (pintype "unspecified"))
    )
    (net (code "58") (name "Net-(U4-XI)") (class "Default")
      (node (ref "C5") (pin "2") (pinfunction "2_2") (pintype "input"))
      (node (ref "U4") (pin "7") (pinfunction "XI_7") (pintype "unspecified"))
      (node (ref "X2") (pin "1") (pinfunction "OSC1_1") (pintype "input"))
    )
    (net (code "59") (name "Net-(U4-XO)") (class "Default")
      (node (ref "C6") (pin "2") (pinfunction "2_2") (pintype "input"))
      (node (ref "U4") (pin "8") (pinfunction "XO_8") (pintype "unspecified"))
      (node (ref "X2") (pin "2") (pinfunction "OSC2_2") (pintype "input"))
    )
    (net (code "60") (name "Net-(U7A-IN_B-)") (class "Default")
      (node (ref "R4") (pin "1") (pinfunction "1_1") (pintype "input"))
      (node (ref "U7") (pin "6") (pinfunction "IN_B-_6") (pintype "unspecified"))
      (node (ref "U7") (pin "7") (pinfunction "OUT_B_7") (pintype "output"))
    )
    (net (code "61") (name "Net-(U8A-TRIMNR)") (class "Default")
      (node (ref "C15") (pin "2") (pinfunction "2_2") (pintype "input"))
      (node (ref "U8") (pin "5") (pinfunction "TRIMNR_5") (pintype "input"))
    )
    (net (code "62") (name "OSC_IN") (class "Default")
      (node (ref "U1") (pin "5") (pinfunction "PF0/OSC_IN/I2C0_SDA_5") (pintype "input"))
      (node (ref "X1") (pin "1") (pinfunction "OSC1_1") (pintype "input"))
    )
    (net (code "63") (name "OSC_OUT") (class "Default")
      (node (ref "U1") (pin "6") (pinfunction "PF1/OSC_OUT/I2C0_SCL_6") (pintype "input"))
      (node (ref "X1") (pin "3") (pinfunction "OSC2_3") (pintype "input"))
    )
    (net (code "64") (name "REF_5V") (class "Default")
      (node (ref "C10") (pin "2") (pinfunction "2_2") (pintype "input"))
      (node (ref "C11") (pin "2") (pinfunction "2_2") (pintype "input"))
      (node (ref "C18") (pin "1") (pinfunction "1_1") (pintype "input"))
      (node (ref "C19") (pin "1") (pinfunction "1_1") (pintype "input"))
      (node (ref "U5") (pin "3") (pinfunction "REF_3") (pintype "input"))
      (node (ref "U8") (pin "6") (pinfunction "VOUT_6") (pintype "output"))
    )
    (net (code "65") (name "RLY1_CTRL") (class "Default")
      (node (ref "R5") (pin "1") (pinfunction "1_1") (pintype "input"))
      (node (ref "U1") (pin "40") (pinfunction "PB4/SPI1_MISO/CMP0_OUT/TIM7_BKIN/ADC_IN11_40") (pintype "input"))
    )
    (net (code "66") (name "RLY2_CTRL") (class "Default")
      (node (ref "R6") (pin "1") (pinfunction "1_1") (pintype "input"))
      (node (ref "U1") (pin "38") (pinfunction "PA15/SPI1_CS/UART1_RX/UART0_RX/CMP0_P0_38") (pintype "input"))
    )
    (net (code "67") (name "RLY3_CTRL") (class "Default")
      (node (ref "R7") (pin "1") (pinfunction "1_1") (pintype "input"))
      (node (ref "U1") (pin "42") (pinfunction "PB6/I2C1_SCL/UART1_TX/UART0_TX/I2C0_SCL/TIM6_CH1N/ADC_IN14/CMP2_N_42") (pintype "input"))
    )
    (net (code "68") (name "RLY4_CTRL") (class "Default")
      (node (ref "R8") (pin "1") (pinfunction "1_1") (pintype "input"))
      (node (ref "U1") (pin "44") (pinfunction "PB2/BEEP1/MCO/CMP1_OUT/ADC_IN9_44") (pintype "input"))
    )
    (net (code "69") (name "RLY5_CTRL") (class "Default")
      (node (ref "R9") (pin "1") (pinfunction "1_1") (pintype "input"))
      (node (ref "U1") (pin "39") (pinfunction "PB3/SPI1_SCK/ADC_IN10/CMP0_N_39") (pintype "input"))
    )
    (net (code "70") (name "RLY6_CTRL") (class "Default")
      (node (ref "R10") (pin "1") (pinfunction "1_1") (pintype "input"))
      (node (ref "U1") (pin "41") (pinfunction "PB5/SPI1_MOSI/TIM6_BKIN/ADC_IN13/CMP2_N_41") (pintype "input"))
    )
    (net (code "71") (name "RLY7_CTRL") (class "Default")
      (node (ref "R11") (pin "1") (pinfunction "1_1") (pintype "input"))
      (node (ref "U1") (pin "43") (pinfunction "PB7/I2C1_SDA/UART1_RX/UART0_RX/I2C0_SDA/CMP2_OUT/TIM7/CJ1N/ADC_IN15_43") (pintype "input"))
    )
    (net (code "72") (name "RLY8_CTRL") (class "Default")
      (node (ref "R12") (pin "1") (pinfunction "1_1") (pintype "input"))
      (node (ref "U1") (pin "45") (pinfunction "PB8/I2C0_SCL/TIM6_CH1/CMP2_P1_45") (pintype "input"))
    )
    (net (code "73") (name "RLY9_CTRL") (class "Default")
      (node (ref "R13") (pin "1") (pinfunction "1_1") (pintype "input"))
      (node (ref "U1") (pin "46") (pinfunction "PB9/IR_TXD/I2C0_SDA/TIM7_CH1/CMP2_P2_46") (pintype "input"))
    )
    (net (code "74") (name "RSTN") (class "Default")
      (node (ref "U1") (pin "7") (pinfunction "NRST_7") (pintype "input"))
      (node (ref "U2") (pin "6") (pinfunction "6_6") (pintype "input"))
    )
    (net (code "75") (name "SPI_CS") (class "Default")
      (node (ref "U1") (pin "25") (pinfunction "PB12/SPI0_CS/TIM1_BKIN/SPI1_CS_25") (pintype "input"))
      (node (ref "U5") (pin "4") (pinfunction "CS#_4") (pintype "input"))
    )
    (net (code "76") (name "SPI_MOSI") (class "Default")
      (node (ref "U1") (pin "28") (pinfunction "PB15/SPI0_MOSI/TIM1_CH3N/SPI1_MOSI/TIM5_CH1N_28") (pintype "input"))
      (node (ref "U5") (pin "6") (pinfunction "DIN_6") (pintype "input"))
    )
    (net (code "77") (name "SPI_SCK") (class "Default")
      (node (ref "U1") (pin "26") (pinfunction "PB13/SPI0_SCK/TIM1_CH1N/SPI1_SCK/I2C1_SDA_26") (pintype "input"))
      (node (ref "U5") (pin "5") (pinfunction "SCLK_5") (pintype "input"))
    )
    (net (code "78") (name "SWCLK") (class "Default")
      (node (ref "U1") (pin "37") (pinfunction "PA14/SWCLK/UART1_TX/UART0_TX_37") (pintype "input"))
      (node (ref "U2") (pin "3") (pinfunction "3_3") (pintype "input"))
    )
    (net (code "79") (name "SWDIO") (class "Default")
      (node (ref "U1") (pin "34") (pinfunction "PA13/SWDIO/IR_TXD_34") (pintype "input"))
      (node (ref "U2") (pin "2") (pinfunction "2_2") (pintype "input"))
    )
    (net (code "80") (name "UART_RX") (class "Default")
      (node (ref "H5") (pin "1") (pinfunction "1_1") (pintype "input"))
      (node (ref "U1") (pin "13") (pinfunction "PA3/UART0_RX/UART1_RX/ADC_IN3/OPA0_P_13") (pintype "input"))
      (node (ref "U2") (pin "5") (pinfunction "5_5") (pintype "input"))
      (node (ref "U4") (pin "2") (pinfunction "TXD_2") (pintype "unspecified"))
    )
    (net (code "81") (name "UART_TX") (class "Default")
      (node (ref "H4") (pin "1") (pinfunction "1_1") (pintype "input"))
      (node (ref "U1") (pin "12") (pinfunction "PA2/UART0_TX/UART1_TX/TIM5_CH1/ADC_IN2/CMP2_P3/OPA1_OUT_12") (pintype "input"))
      (node (ref "U2") (pin "4") (pinfunction "4_4") (pintype "input"))
      (node (ref "U4") (pin "3") (pinfunction "RXD_3") (pintype "unspecified"))
    )
    (net (code "82") (name "USB_D+") (class "Default")
      (node (ref "U4") (pin "5") (pinfunction "UD+_5") (pintype "unspecified"))
      (node (ref "USB1") (pin "3") (pinfunction "D+_3") (pintype "input"))
    )
    (net (code "83") (name "USB_D-") (class "Default")
      (node (ref "U4") (pin "6") (pinfunction "UD-_6") (pintype "unspecified"))
      (node (ref "USB1") (pin "2") (pinfunction "D-_2") (pintype "input"))
    )
    (net (code "84") (name "unconnected-(K1-Pad1)") (class "Default")
      (node (ref "K1") (pin "1") (pinfunction "1_1") (pintype "input"))
    )
    (net (code "85") (name "unconnected-(K1-Pad2)") (class "Default")
      (node (ref "K1") (pin "2") (pinfunction "2_2") (pintype "input"))
    )
    (net (code "86") (name "unconnected-(K1-Pad3)") (class "Default")
      (node (ref "K1") (pin "3") (pinfunction "3_3") (pintype "input"))
    )
    (net (code "87") (name "unconnected-(K1-Pad4)") (class "Default")
      (node (ref "K1") (pin "4") (pinfunction "4_4") (pintype "input"))
    )
    (net (code "88") (name "unconnected-(K1-Pad5)") (class "Default")
      (node (ref "K1") (pin "5") (pinfunction "5_5") (pintype "input"))
    )
    (net (code "89") (name "unconnected-(RELAY1-Pad3)") (class "Default")
      (node (ref "RELAY1") (pin "3") (pinfunction "3_3") (pintype "input+no_connect"))
    )
    (net (code "90") (name "unconnected-(RELAY2-Pad3)") (class "Default")
      (node (ref "RELAY2") (pin "3") (pinfunction "3_3") (pintype "input+no_connect"))
    )
    (net (code "91") (name "unconnected-(RELAY3-Pad3)") (class "Default")
      (node (ref "RELAY3") (pin "3") (pinfunction "3_3") (pintype "input+no_connect"))
    )
    (net (code "92") (name "unconnected-(RELAY4-Pad3)") (class "Default")
      (node (ref "RELAY4") (pin "3") (pinfunction "3_3") (pintype "input+no_connect"))
    )
    (net (code "93") (name "unconnected-(RELAY5-Pad3)") (class "Default")
      (node (ref "RELAY5") (pin "3") (pinfunction "3_3") (pintype "input+no_connect"))
    )
    (net (code "94") (name "unconnected-(RELAY6-Pad3)") (class "Default")
      (node (ref "RELAY6") (pin "3") (pinfunction "3_3") (pintype "input+no_connect"))
    )
    (net (code "95") (name "unconnected-(RELAY7-Pad3)") (class "Default")
      (node (ref "RELAY7") (pin "3") (pinfunction "3_3") (pintype "input+no_connect"))
    )
    (net (code "96") (name "unconnected-(RELAY8-Pad3)") (class "Default")
      (node (ref "RELAY8") (pin "3") (pinfunction "3_3") (pintype "input+no_connect"))
    )
    (net (code "97") (name "unconnected-(RELAY9-Pad3)") (class "Default")
      (node (ref "RELAY9") (pin "3") (pinfunction "3_3") (pintype "input+no_connect"))
    )
    (net (code "98") (name "unconnected-(U1-PA0{slash}ADC_IN0{slash}VREF+{slash}CMP1_P{slash}OPA1_P-Pad10)") (class "Default")
      (node (ref "U1") (pin "10") (pinfunction "PA0/ADC_IN0/VREF+/CMP1_P/OPA1_P_10") (pintype "input+no_connect"))
    )
    (net (code "99") (name "unconnected-(U1-PA1{slash}ADC_IN1{slash}CMP1_N{slash}OPA1_N-Pad11)") (class "Default")
      (node (ref "U1") (pin "11") (pinfunction "PA1/ADC_IN1/CMP1_N/OPA1_N_11") (pintype "input+no_connect"))
    )
    (net (code "100") (name "unconnected-(U1-PA4{slash}SPI0_CS{slash}UART1_TX{slash}UART0_TX-Pad14)") (class "Default")
      (node (ref "U1") (pin "14") (pinfunction "PA4/SPI0_CS/UART1_TX/UART0_TX_14") (pintype "input+no_connect"))
    )
    (net (code "101") (name "unconnected-(U1-PA5{slash}SPI0_SCK{slash}UART1_RX{slash}UART0_RX{slash}ADC_IN5{slash}CMP0_P3{slash}OPA0_OUT-Pad15)") (class "Default")
      (node (ref "U1") (pin "15") (pinfunction "PA5/SPI0_SCK/UART1_RX/UART0_RX/ADC_IN5/CMP0_P3/OPA0_OUT_15") (pintype "input+no_connect"))
    )
    (net (code "102") (name "unconnected-(U1-PA6{slash}SPI0_MISO{slash}TIM1_BKIN{slash}TIM6{slash}CH1{slash}ADC_IN6-Pad16)") (class "Default")
      (node (ref "U1") (pin "16") (pinfunction "PA6/SPI0_MISO/TIM1_BKIN/TIM6/CH1/ADC_IN6_16") (pintype "input+no_connect"))
    )
    (net (code "103") (name "unconnected-(U1-PA7{slash}SPI0_MOSI{slash}TIM1_CJ1N{slash}ADC_ETR{slash}TIM7_CH1{slash}ADC_IN7-Pad17)") (class "Default")
      (node (ref "U1") (pin "17") (pinfunction "PA7/SPI0_MOSI/TIM1_CJ1N/ADC_ETR/TIM7_CH1/ADC_IN7_17") (pintype "input+no_connect"))
    )
    (net (code "104") (name "unconnected-(U1-PA11{slash}I2C1_SCL{slash}TIM1_CH4{slash}I2C0_SCL-Pad32)") (class "Default")
      (node (ref "U1") (pin "32") (pinfunction "PA11/I2C1_SCL/TIM1_CH4/I2C0_SCL_32") (pintype "input+no_connect"))
    )
    (net (code "105") (name "unconnected-(U1-PA12{slash}I2C1_SDA{slash}TIM1_CH4N{slash}I2C0_SDA{slash}TIM1_ETR-Pad33)") (class "Default")
      (node (ref "U1") (pin "33") (pinfunction "PA12/I2C1_SDA/TIM1_CH4N/I2C0_SDA/TIM1_ETR_33") (pintype "input+no_connect"))
    )
    (net (code "106") (name "unconnected-(U1-PB0{slash}TIM1_CH2N{slash}ADC_IN12-Pad18)") (class "Default")
      (node (ref "U1") (pin "18") (pinfunction "PB0/TIM1_CH2N/ADC_IN12_18") (pintype "input+no_connect"))
    )
    (net (code "107") (name "unconnected-(U1-PB1{slash}IR_TXD{slash}TIM1_3N{slash}ADC_IN8-Pad19)") (class "Default")
      (node (ref "U1") (pin "19") (pinfunction "PB1/IR_TXD/TIM1_3N/ADC_IN8_19") (pintype "input+no_connect"))
    )
    (net (code "108") (name "unconnected-(U1-PB10{slash}SPI1_SCK{slash}I2C0_SCL{slash}I2C1_SCL{slash}TIM6_CH1{slash}CMP_P1-Pad21)") (class "Default")
      (node (ref "U1") (pin "21") (pinfunction "PB10/SPI1_SCK/I2C0_SCL/I2C1_SCL/TIM6_CH1/CMP_P1_21") (pintype "input+no_connect"))
    )
    (net (code "109") (name "unconnected-(U1-PB11{slash}I2C0_SDA{slash}I2C1_SDA{slash}TIM7_CH1{slash}CMP0_P2-Pad22)") (class "Default")
      (node (ref "U1") (pin "22") (pinfunction "PB11/I2C0_SDA/I2C1_SDA/TIM7_CH1/CMP0_P2_22") (pintype "input+no_connect"))
    )
    (net (code "110") (name "unconnected-(U1-PB14{slash}SPI0_MISO{slash}TIM1_CH2N{slash}SPI1_MISO{slash}TIM5_CH1-Pad27)") (class "Default")
      (node (ref "U1") (pin "27") (pinfunction "PB14/SPI0_MISO/TIM1_CH2N/SPI1_MISO/TIM5_CH1_27") (pintype "input+no_connect"))
    )
    (net (code "111") (name "unconnected-(U1-PF2{slash}TIM5_CH1-Pad20)") (class "Default")
      (node (ref "U1") (pin "20") (pinfunction "PF2/TIM5_CH1_20") (pintype "input+no_connect"))
    )
    (net (code "112") (name "unconnected-(U1-PF6{slash}I2C1_SCL{slash}I2C0_SCL-Pad35)") (class "Default")
      (node (ref "U1") (pin "35") (pinfunction "PF6/I2C1_SCL/I2C0_SCL_35") (pintype "input+no_connect"))
    )
    (net (code "113") (name "unconnected-(U1-PF7{slash}I2C1_SDA{slash}I2C0_SDA-Pad36)") (class "Default")
      (node (ref "U1") (pin "36") (pinfunction "PF7/I2C1_SDA/I2C0_SDA_36") (pintype "input+no_connect"))
    )
    (net (code "114") (name "unconnected-(U4-CTS#-Pad9)") (class "Default")
      (node (ref "U4") (pin "9") (pinfunction "CTS#_9") (pintype "unspecified+no_connect"))
    )
    (net (code "115") (name "unconnected-(U4-DCD#-Pad12)") (class "Default")
      (node (ref "U4") (pin "12") (pinfunction "DCD#_12") (pintype "unspecified+no_connect"))
    )
    (net (code "116") (name "unconnected-(U4-DSR#-Pad10)") (class "Default")
      (node (ref "U4") (pin "10") (pinfunction "DSR#_10") (pintype "unspecified+no_connect"))
    )
    (net (code "117") (name "unconnected-(U4-DTR#-Pad13)") (class "Default")
      (node (ref "U4") (pin "13") (pinfunction "DTR#_13") (pintype "unspecified+no_connect"))
    )
    (net (code "118") (name "unconnected-(U4-R232-Pad15)") (class "Default")
      (node (ref "U4") (pin "15") (pinfunction "R232_15") (pintype "unspecified+no_connect"))
    )
    (net (code "119") (name "unconnected-(U4-RI#-Pad11)") (class "Default")
      (node (ref "U4") (pin "11") (pinfunction "RI#_11") (pintype "unspecified+no_connect"))
    )
    (net (code "120") (name "unconnected-(U4-RTS#-Pad14)") (class "Default")
      (node (ref "U4") (pin "14") (pinfunction "RTS#_14") (pintype "unspecified+no_connect"))
    )
    (net (code "121") (name "unconnected-(U7B-IN_A+-Pad3)") (class "Default")
      (node (ref "U7") (pin "3") (pinfunction "IN_A+_3") (pintype "unspecified+no_connect"))
    )
    (net (code "122") (name "unconnected-(U7B-IN_A--Pad2)") (class "Default")
      (node (ref "U7") (pin "2") (pinfunction "IN_A-_2") (pintype "unspecified+no_connect"))
    )
    (net (code "123") (name "unconnected-(U7B-OUT_A-Pad1)") (class "Default")
      (node (ref "U7") (pin "1") (pinfunction "OUT_A_1") (pintype "output+no_connect"))
    )
    (net (code "124") (name "unconnected-(U8A-TEMP-Pad3)") (class "Default")
      (node (ref "U8") (pin "3") (pinfunction "TEMP_3") (pintype "output+no_connect"))
    )
    (net (code "125") (name "unconnected-(U8B-DNC-Pad1)") (class "Default")
      (node (ref "U8") (pin "1") (pinfunction "DNC_1") (pintype "input+no_connect"))
    )
    (net (code "126") (name "unconnected-(U8B-DNC-Pad8)") (class "Default")
      (node (ref "U8") (pin "8") (pinfunction "DNC_8") (pintype "input+no_connect"))
    )
    (net (code "127") (name "unconnected-(U8B-NC-Pad7)") (class "Default")
      (node (ref "U8") (pin "7") (pinfunction "NC_7") (pintype "input+no_connect"))
    )
  )
)
